# Module_BaseBoard.net
KiCad netlist of a schematic drawn in EAGLE
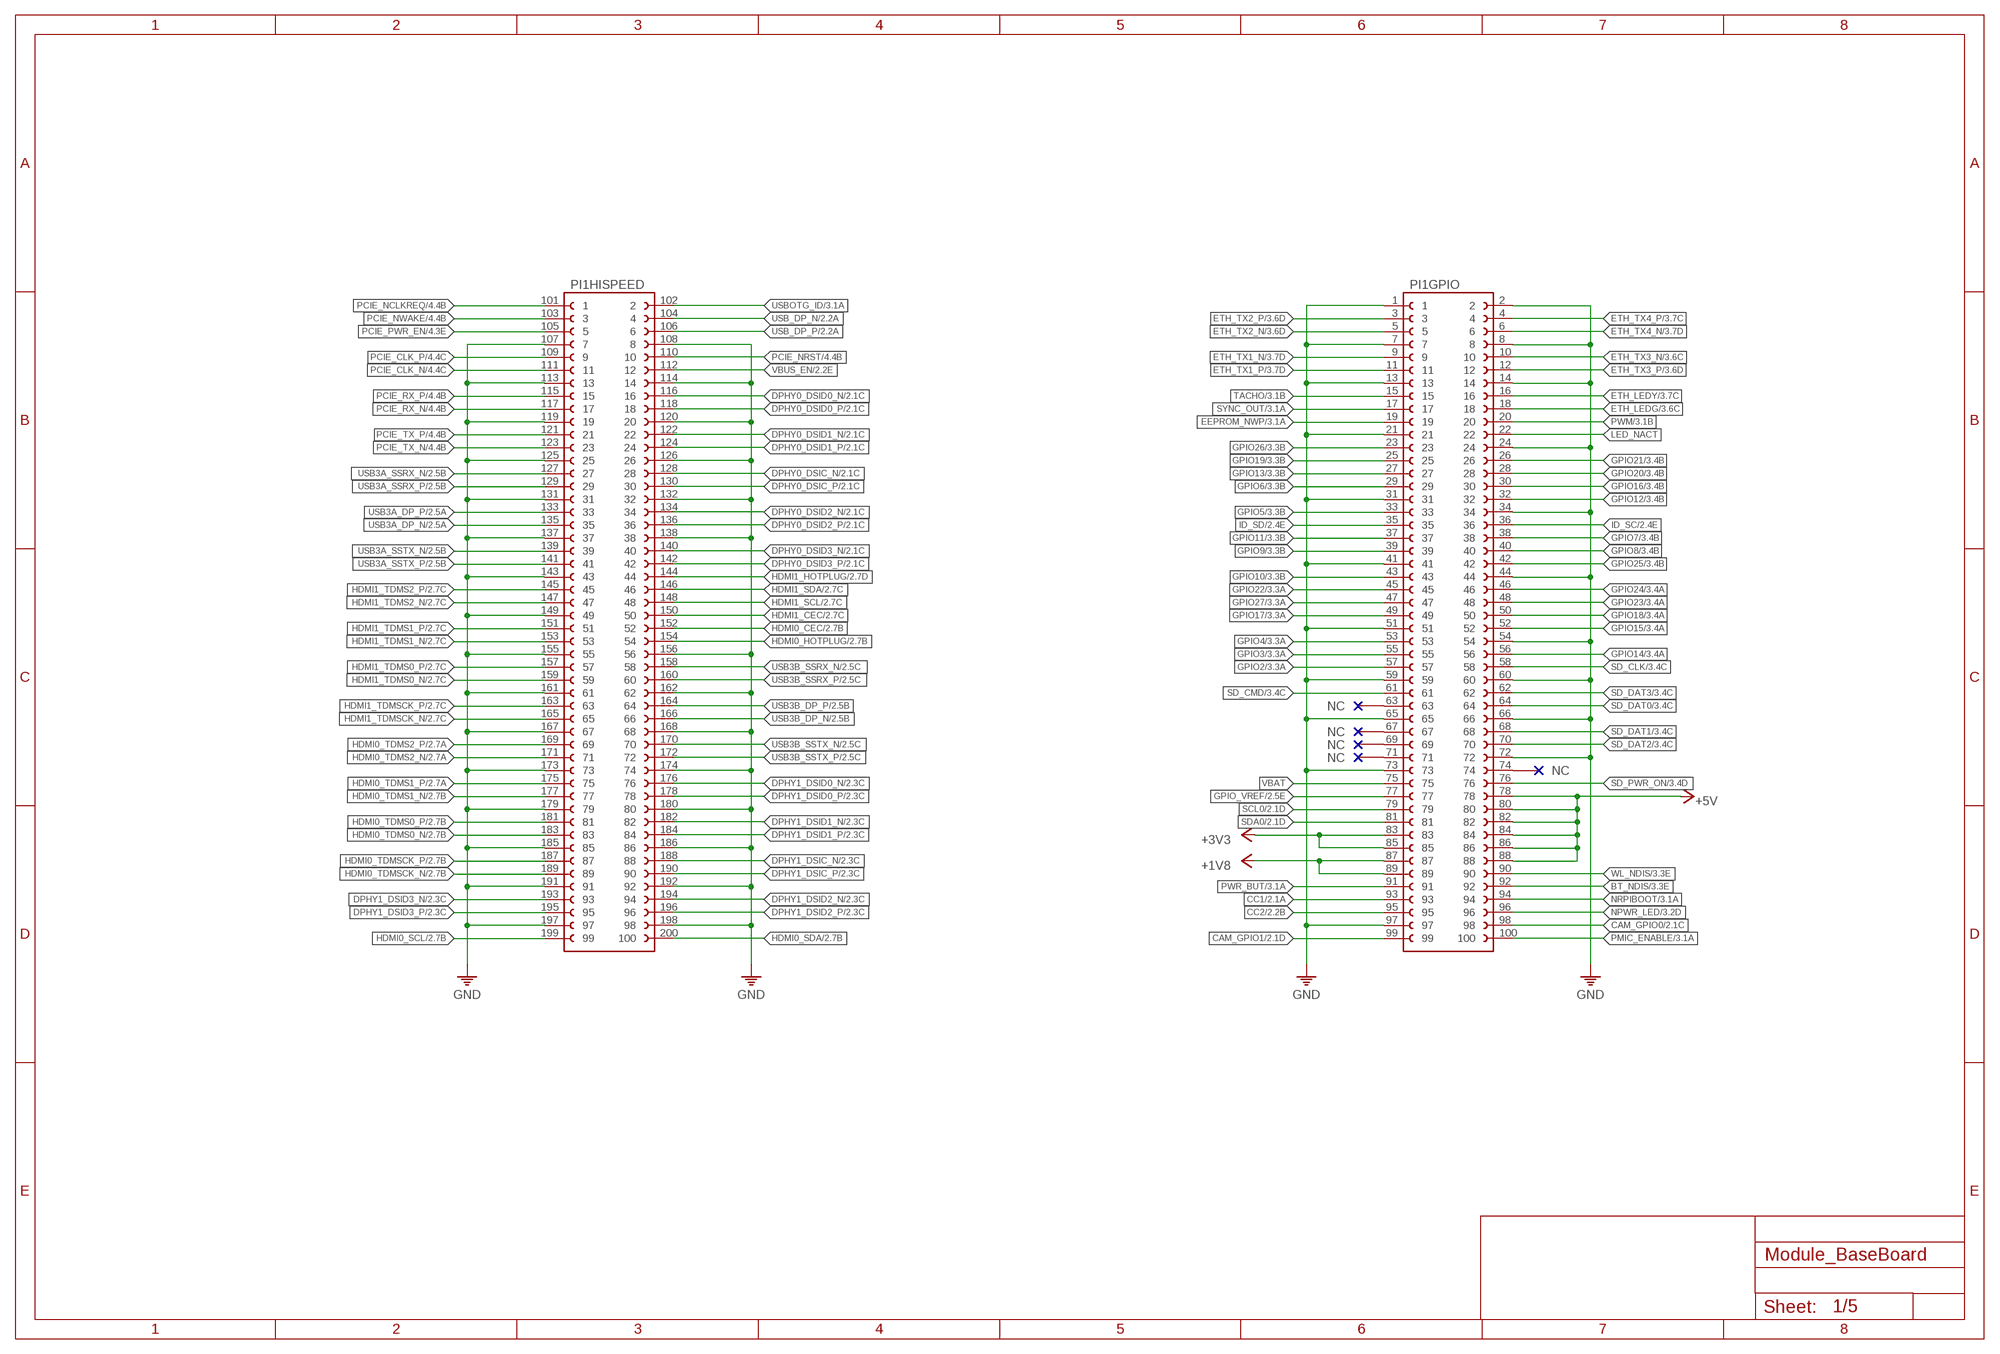
[diagram p0: schematic, sheet 1]
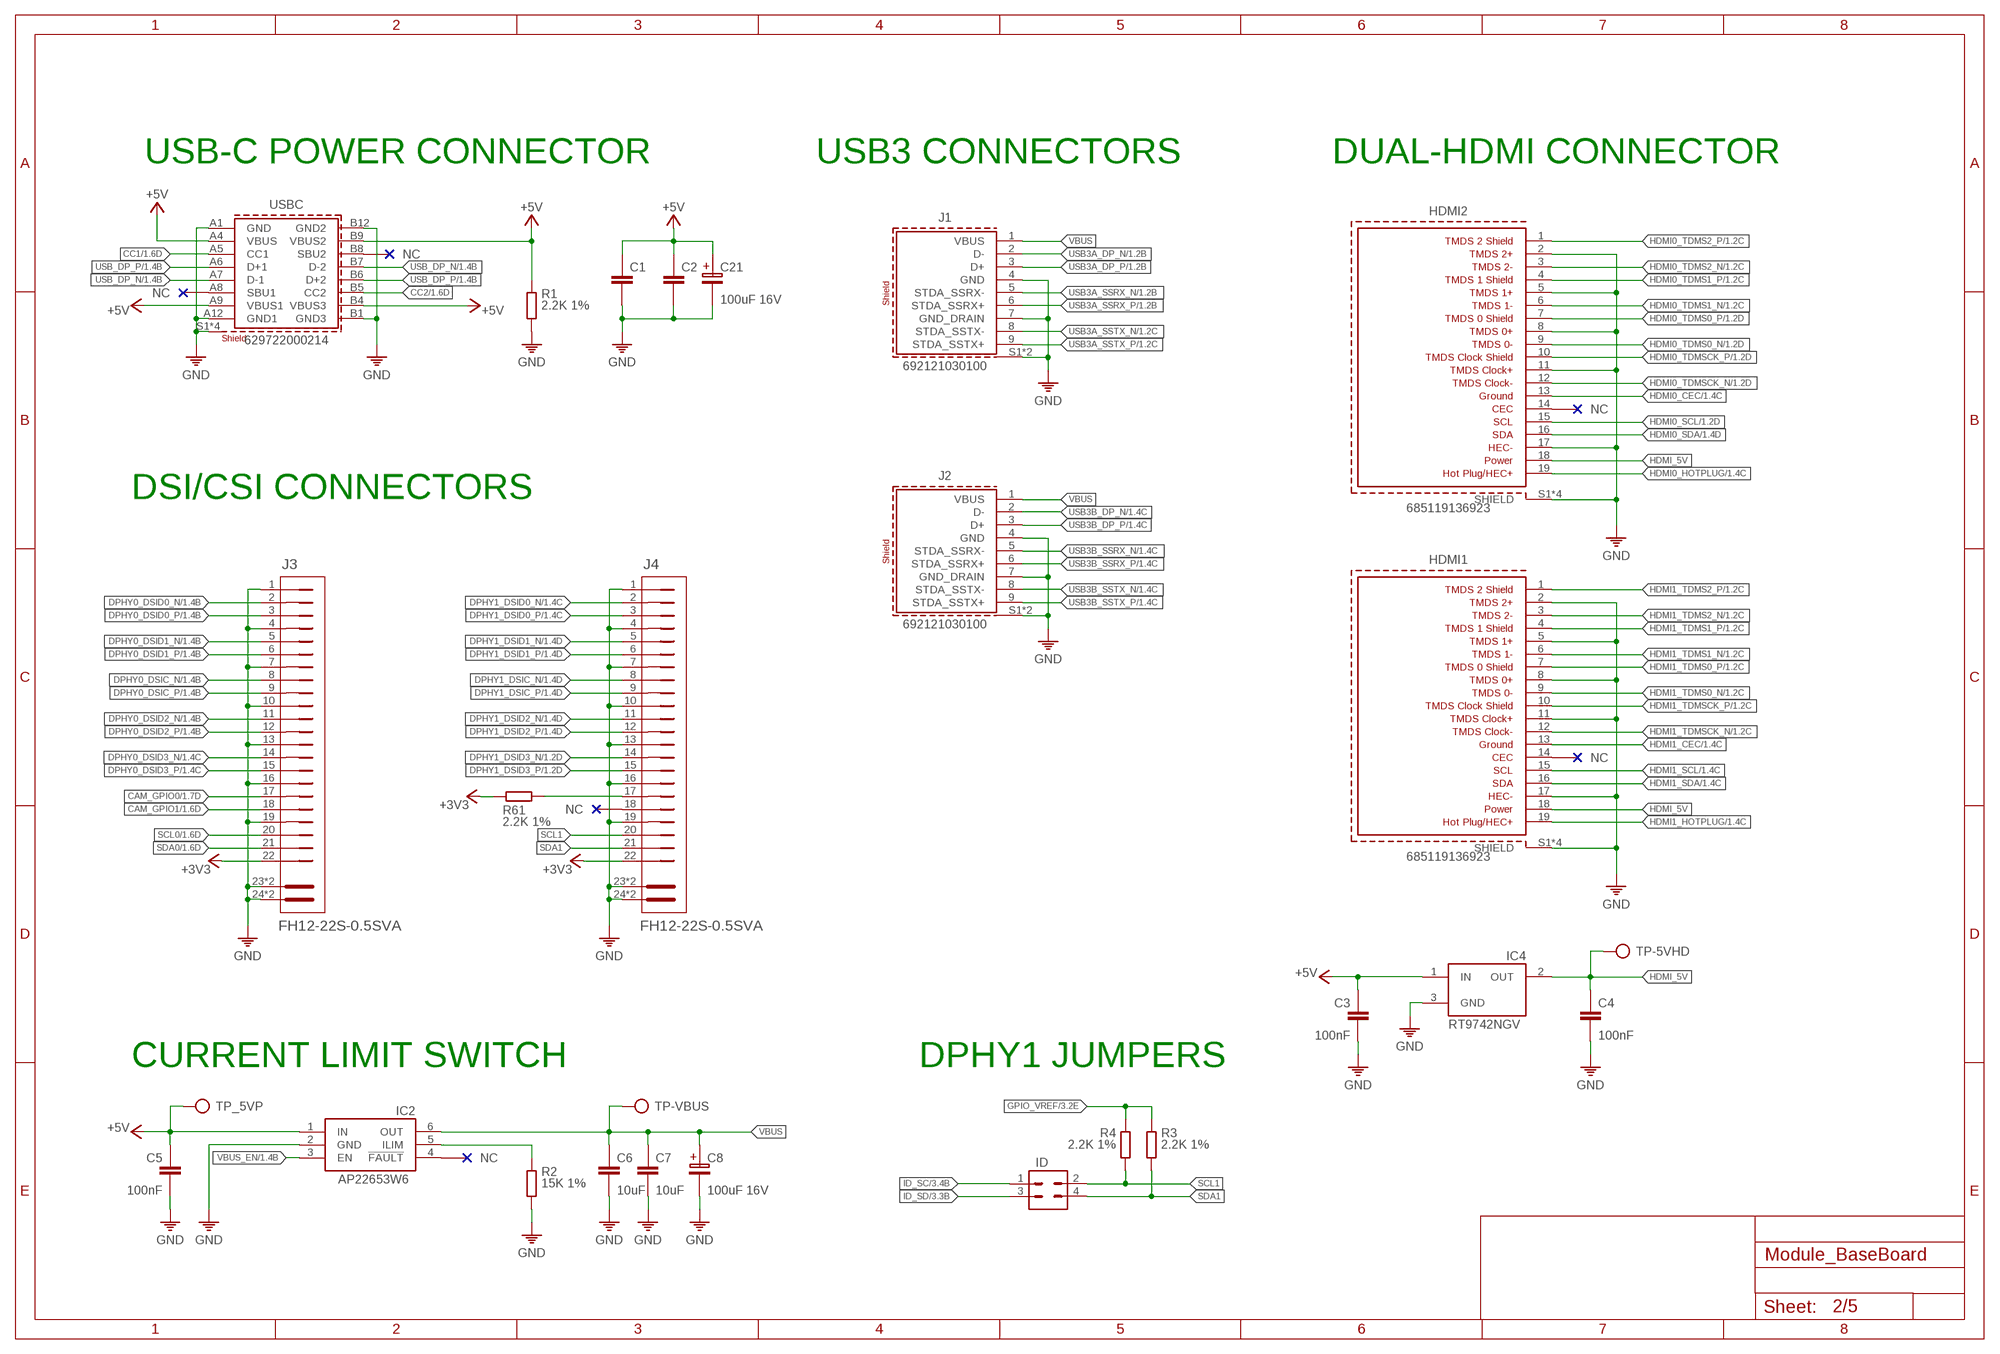
[diagram p1: schematic, sheet 2]
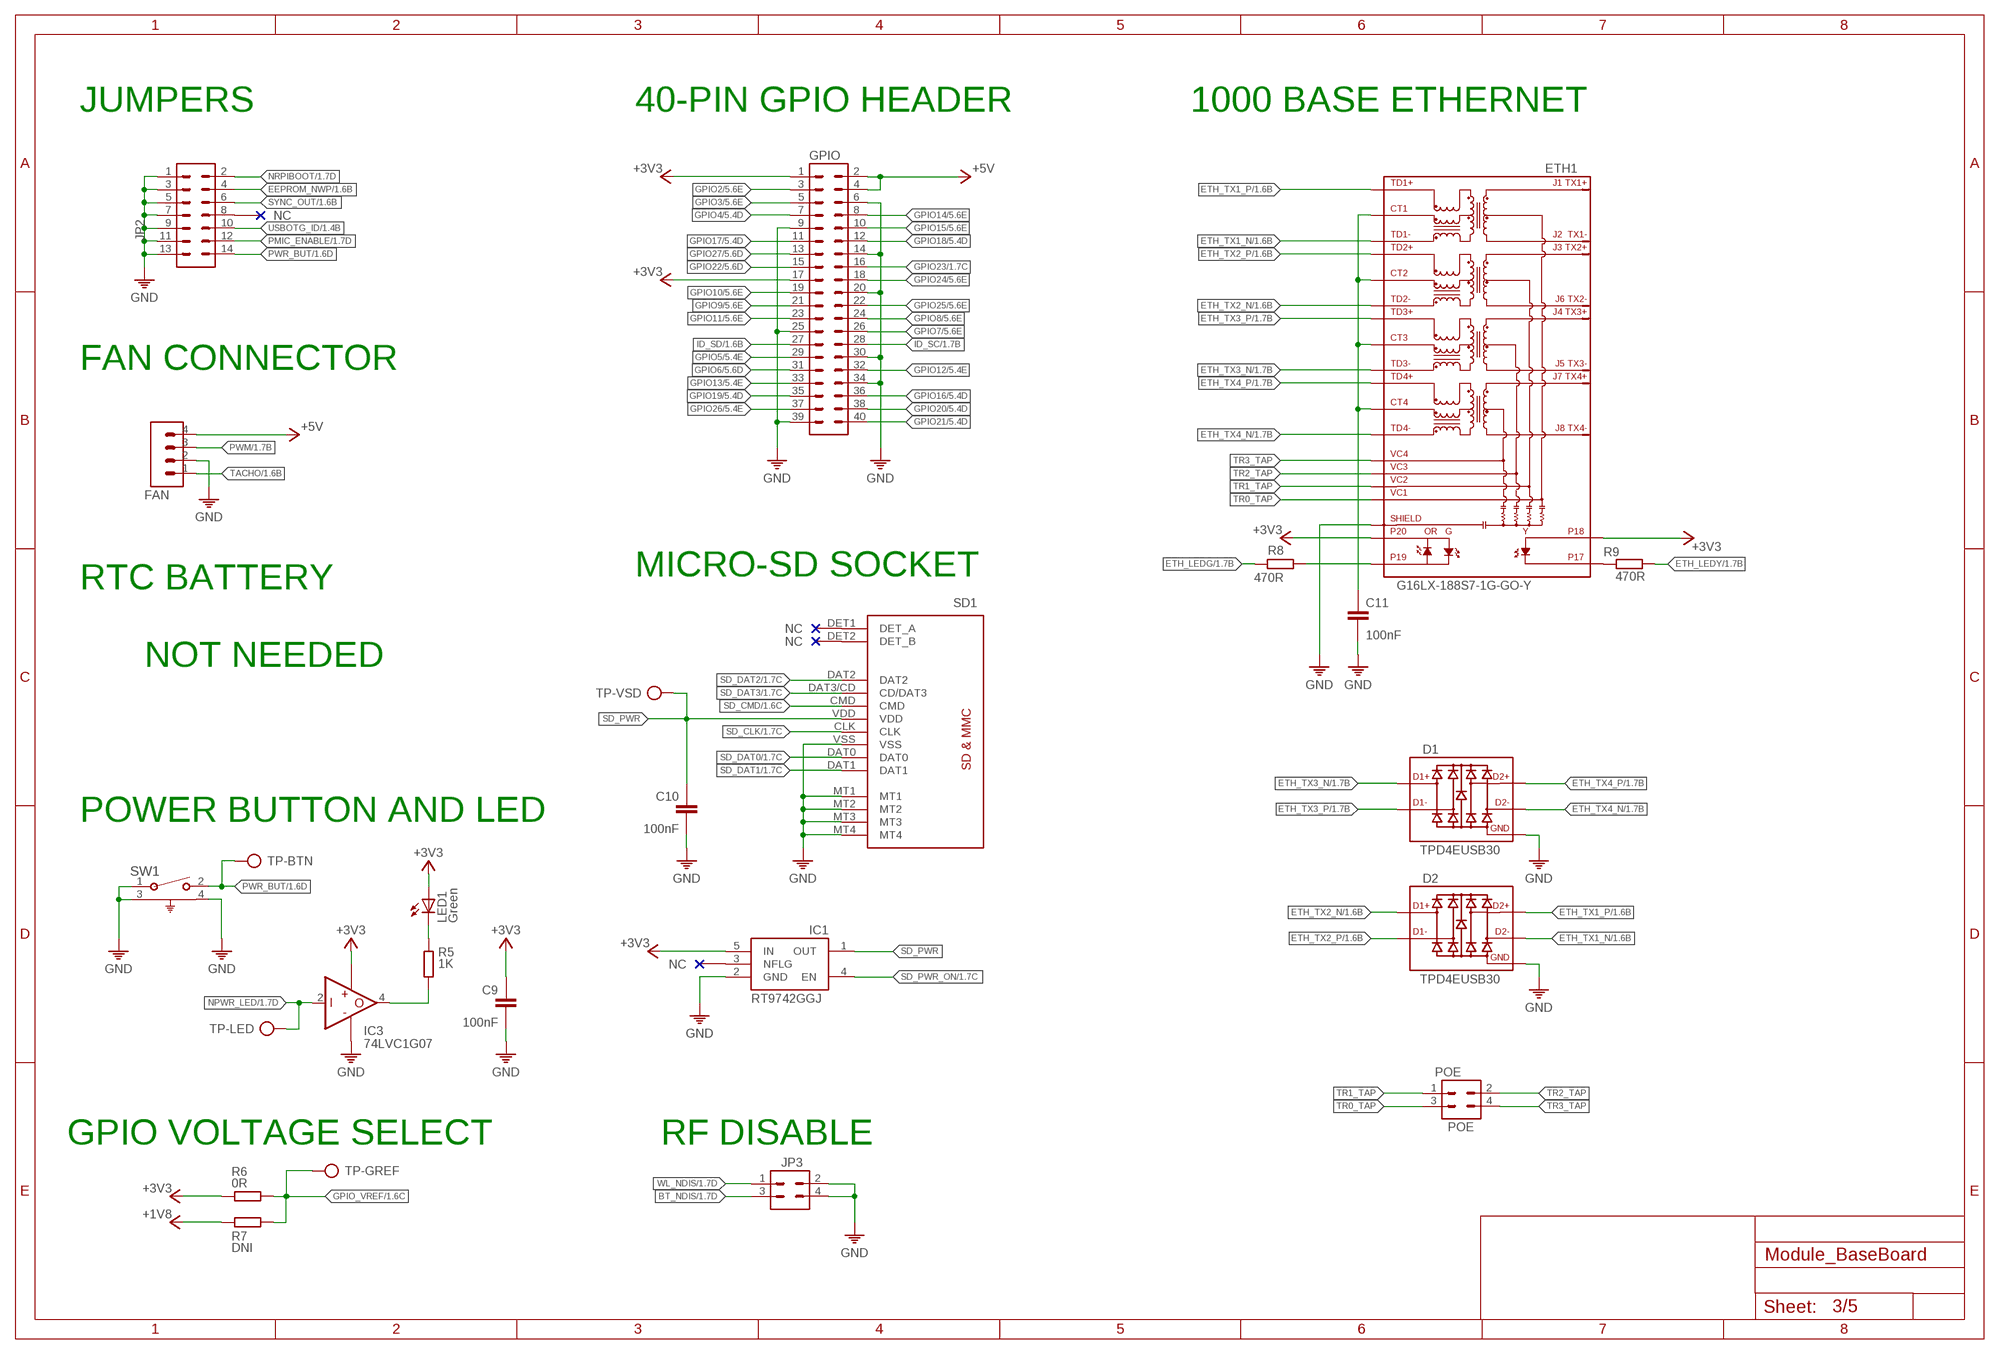
[diagram p2: schematic, sheet 3]
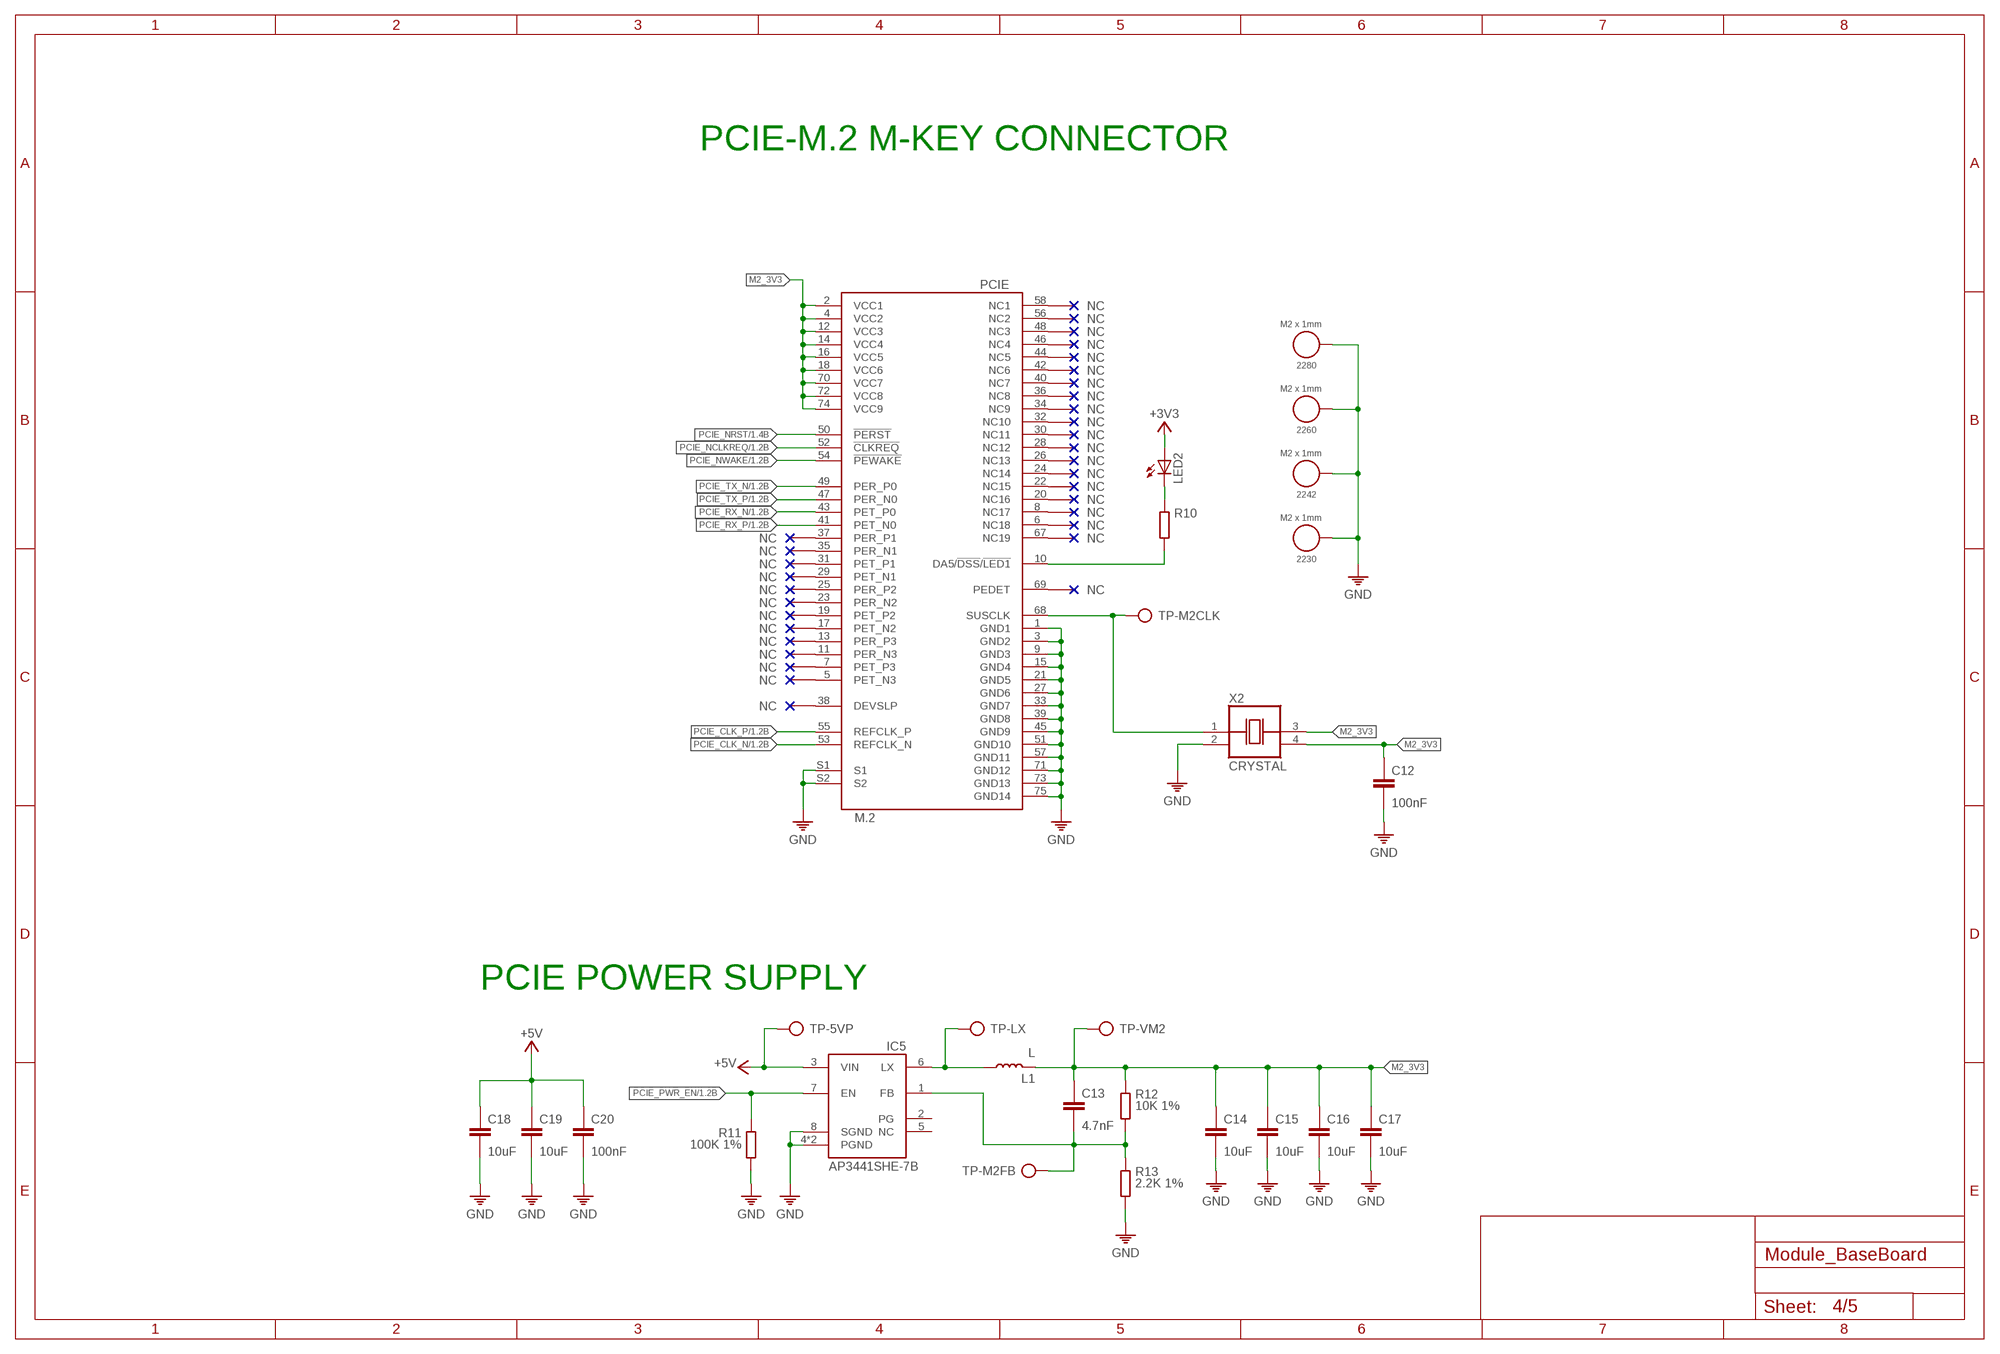
[diagram p3: schematic, sheet 4]
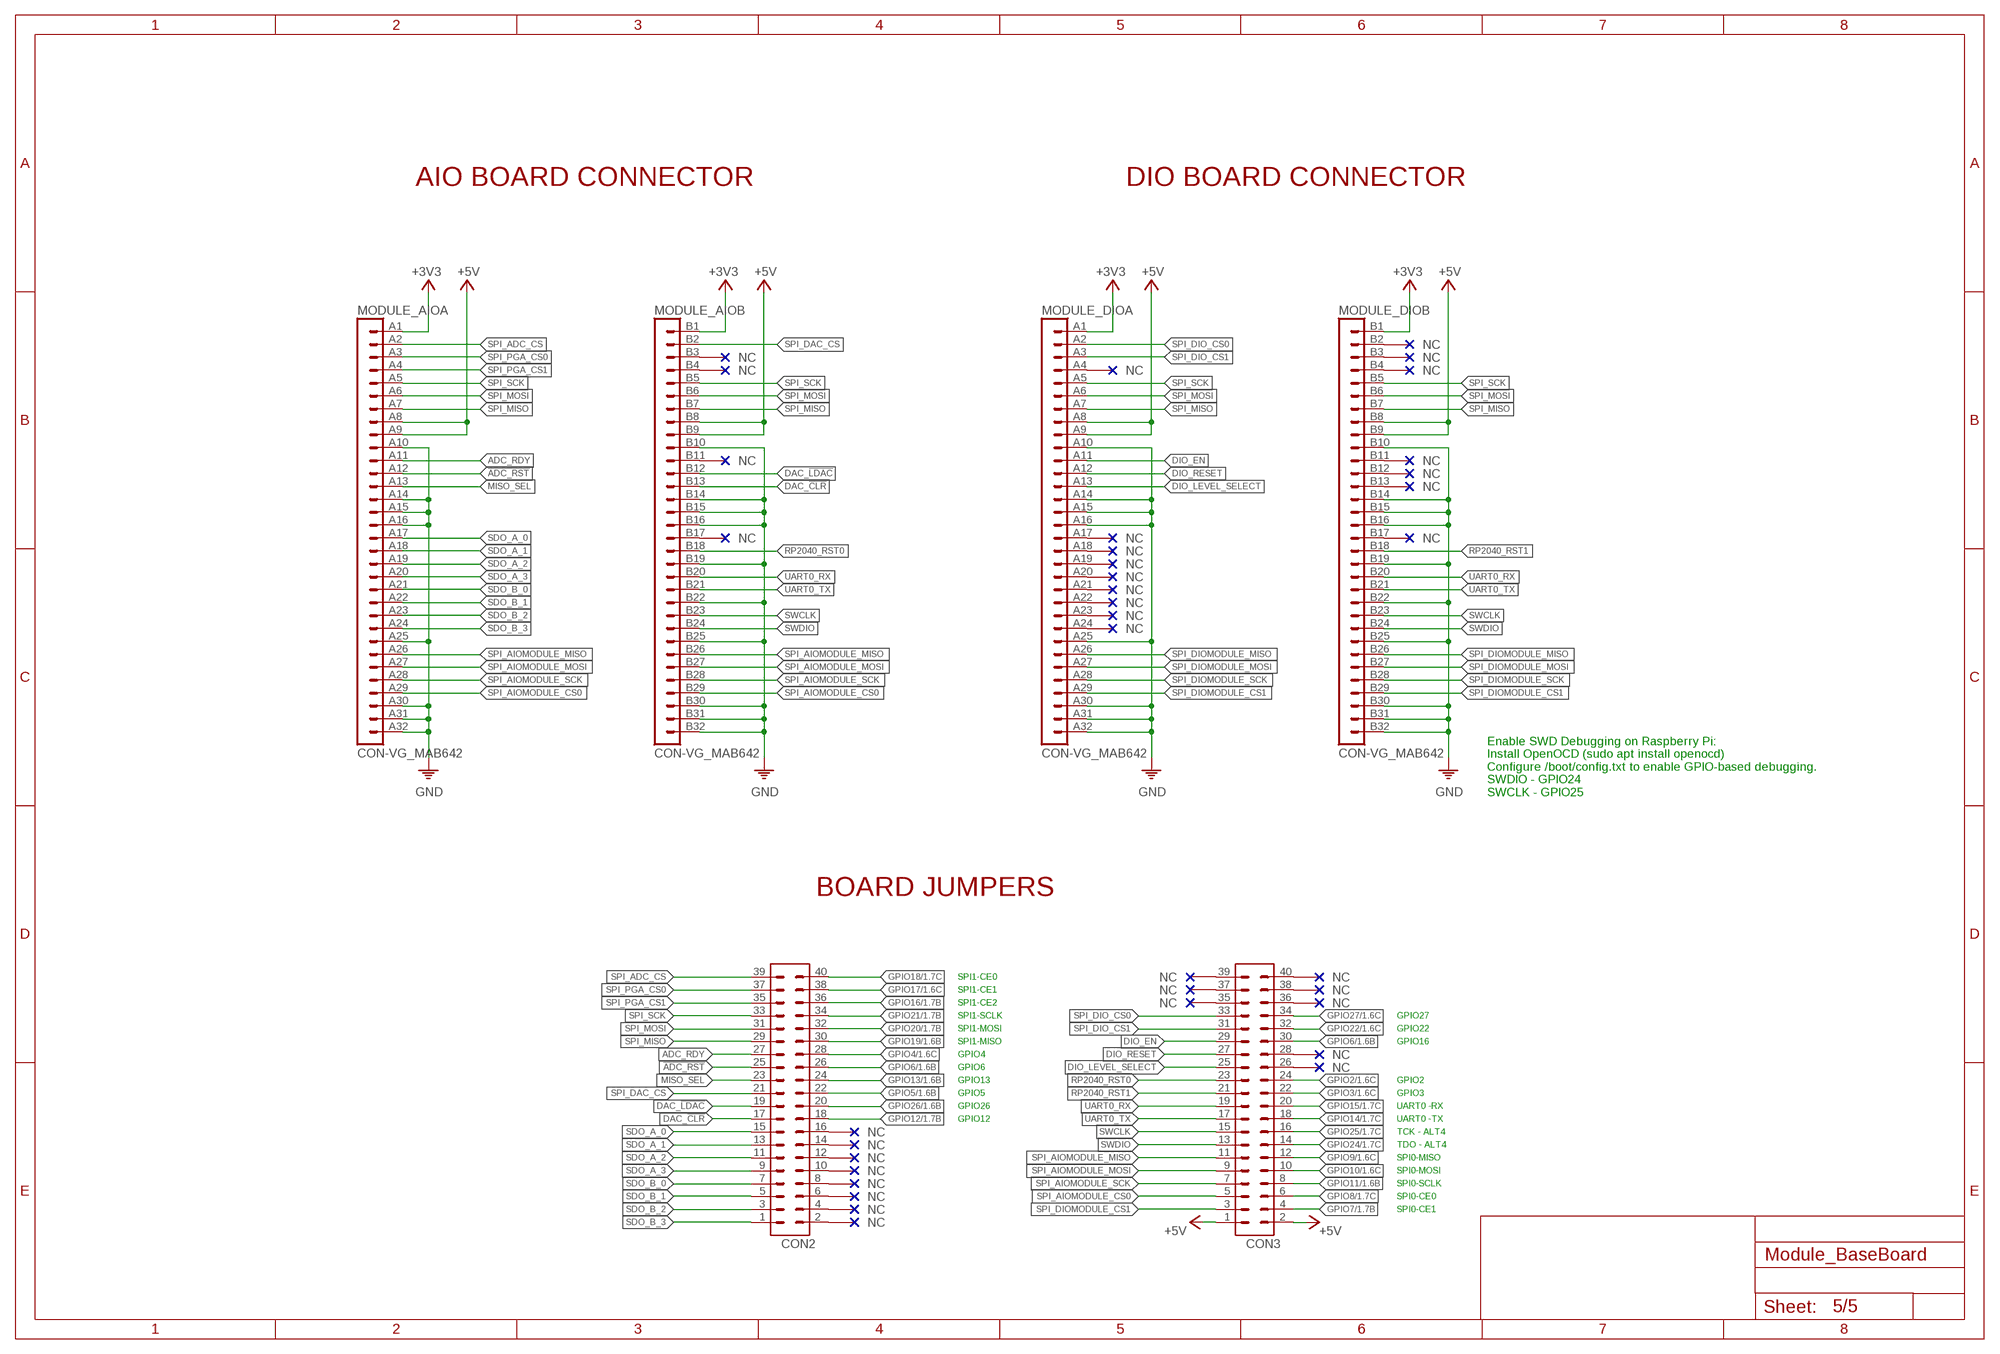
[diagram p4: schematic, sheet 5]

(export (version "E")
  (design (tool "Eeschema 10.0.6"))
  (components
    (comp (ref "2230")
      (value "M2 x 1mm")
      (footprint "eagle-import:WA-SMSI_9774010243")
      (libsource (lib "eagle-import") (part "WA-SMSI_9774XXX243_9774010243"))
    )
    (comp (ref "2242")
      (value "M2 x 1mm")
      (footprint "eagle-import:WA-SMSI_9774010243")
      (libsource (lib "eagle-import") (part "WA-SMSI_9774XXX243_9774010243"))
    )
    (comp (ref "2260")
      (value "M2 x 1mm")
      (footprint "eagle-import:WA-SMSI_9774010243")
      (libsource (lib "eagle-import") (part "WA-SMSI_9774XXX243_9774010243"))
    )
    (comp (ref "2280")
      (value "M2 x 1mm")
      (footprint "eagle-import:WA-SMSI_9774010243")
      (libsource (lib "eagle-import") (part "WA-SMSI_9774XXX243_9774010243"))
    )
    (comp (ref "C12")
      (value "100nF")
      (footprint "eagle-import:C0402")
      (libsource (lib "eagle-import") (part "C-0402"))
    )
    (comp (ref "C13")
      (value "4.7nF")
      (footprint "eagle-import:C0402")
      (libsource (lib "eagle-import") (part "C-0402"))
    )
    (comp (ref "C14")
      (value "10uF")
      (footprint "eagle-import:C0805")
      (libsource (lib "eagle-import") (part "C-0805"))
    )
    (comp (ref "C15")
      (value "10uF")
      (footprint "eagle-import:C0805")
      (libsource (lib "eagle-import") (part "C-0805"))
    )
    (comp (ref "C16")
      (value "10uF")
      (footprint "eagle-import:C0805")
      (libsource (lib "eagle-import") (part "C-0805"))
    )
    (comp (ref "C17")
      (value "10uF")
      (footprint "eagle-import:C0805")
      (libsource (lib "eagle-import") (part "C-0805"))
    )
    (comp (ref "C18")
      (value "10uF")
      (footprint "eagle-import:C0805")
      (libsource (lib "eagle-import") (part "C-0805"))
    )
    (comp (ref "C19")
      (value "10uF")
      (footprint "eagle-import:C0805")
      (libsource (lib "eagle-import") (part "C-0805"))
    )
    (comp (ref "C20")
      (value "100nF")
      (footprint "eagle-import:C0402")
      (libsource (lib "eagle-import") (part "C-0402"))
    )
    (comp (ref "IC5")
      (value "AP3441SHE-7B")
      (footprint "eagle-import:SON50P201X201X56-9T90X170N")
      (libsource (lib "eagle-import") (part "AP3441SHE-7B"))
    )
    (comp (ref "L1")
      (value "L")
      (footprint "eagle-import:SRR5228A")
      (libsource (lib "eagle-import") (part "L"))
    )
    (comp (ref "LED2")
      (value "LEDCHIPLED_0805")
      (footprint "eagle-import:CHIPLED_0805")
      (libsource (lib "eagle-import") (part "LEDCHIPLED_0805"))
    )
    (comp (ref "PCIE")
      (value "M.2")
      (footprint "eagle-import:M.2")
      (libsource (lib "eagle-import") (part "M.2"))
    )
    (comp (ref "R10")
      (value "R0402")
      (footprint "eagle-import:0402")
      (libsource (lib "eagle-import") (part "R0402"))
    )
    (comp (ref "R11")
      (value "100K 1%")
      (footprint "eagle-import:0402")
      (libsource (lib "eagle-import") (part "R0402"))
    )
    (comp (ref "R12")
      (value "10K 1%")
      (footprint "eagle-import:0402")
      (libsource (lib "eagle-import") (part "R0402"))
    )
    (comp (ref "R13")
      (value "2.2K 1%")
      (footprint "eagle-import:0402")
      (libsource (lib "eagle-import") (part "R0402"))
    )
    (comp (ref "TP-5VP")
      (value "TP")
      (footprint "eagle-import:TP")
      (libsource (lib "eagle-import") (part "TP"))
    )
    (comp (ref "TP-LX")
      (value "TP")
      (footprint "eagle-import:TP")
      (libsource (lib "eagle-import") (part "TP"))
    )
    (comp (ref "TP-M2CLK")
      (value "TP")
      (footprint "eagle-import:TP")
      (libsource (lib "eagle-import") (part "TP"))
    )
    (comp (ref "TP-M2FB")
      (value "TP")
      (footprint "eagle-import:TP")
      (libsource (lib "eagle-import") (part "TP"))
    )
    (comp (ref "TP-VM2")
      (value "TP")
      (footprint "eagle-import:TP")
      (libsource (lib "eagle-import") (part "TP"))
    )
    (comp (ref "X2")
      (value "CRYSTAL")
      (footprint "eagle-import:OSCCC500X320X130")
      (libsource (lib "eagle-import") (part "CRYSTAL"))
    )
    (comp (ref "C9")
      (value "100nF")
      (footprint "eagle-import:C0402")
      (libsource (lib "eagle-import") (part "C-0402"))
    )
    (comp (ref "C10")
      (value "100nF")
      (footprint "eagle-import:C0402")
      (libsource (lib "eagle-import") (part "C-0402"))
    )
    (comp (ref "C11")
      (value "100nF")
      (footprint "eagle-import:C0402")
      (libsource (lib "eagle-import") (part "C-0402"))
    )
    (comp (ref "D1")
      (value "TPD4EUSB30")
      (footprint "eagle-import:USON")
      (libsource (lib "eagle-import") (part "TPD4EUSB30"))
    )
    (comp (ref "D2")
      (value "TPD4EUSB30")
      (footprint "eagle-import:USON")
      (libsource (lib "eagle-import") (part "TPD4EUSB30"))
    )
    (comp (ref "ETH1")
      (value "G16LX-188S7-1G-GO-Y")
      (footprint "eagle-import:MAGJACK_POE")
      (libsource (lib "eagle-import") (part "MAGJACK-POE"))
    )
    (comp (ref "FAN")
      (value "CON-1X4")
      (footprint "eagle-import:1X4")
      (libsource (lib "eagle-import") (part "CON-1X4"))
    )
    (comp (ref "GPIO")
      (value "CON-2X20")
      (footprint "eagle-import:2X20")
      (libsource (lib "eagle-import") (part "CON-2X20"))
    )
    (comp (ref "IC1")
      (value "RT9742GGJ")
      (footprint "eagle-import:SOT23-5")
      (libsource (lib "eagle-import") (part "RT9742GGJ5"))
    )
    (comp (ref "IC3")
      (value "74LVC1G07")
      (footprint "eagle-import:SOT23-5")
      (libsource (lib "eagle-import") (part "74LVC1G07"))
    )
    (comp (ref "JP2")
      (value "CON-2X7")
      (footprint "eagle-import:2X7")
      (libsource (lib "eagle-import") (part "CON-2X7"))
    )
    (comp (ref "JP3")
      (value "CON-2X2")
      (footprint "eagle-import:2X2")
      (libsource (lib "eagle-import") (part "CON-2X2"))
    )
    (comp (ref "LED1")
      (value "Green")
      (footprint "eagle-import:CHIPLED_0805")
      (libsource (lib "eagle-import") (part "LEDCHIPLED_0805"))
    )
    (comp (ref "POE")
      (value "POE")
      (footprint "eagle-import:2X2")
      (libsource (lib "eagle-import") (part "CON-2X2"))
    )
    (comp (ref "R5")
      (value "1K")
      (footprint "eagle-import:0402")
      (libsource (lib "eagle-import") (part "R0402"))
    )
    (comp (ref "R6")
      (value "0R")
      (footprint "eagle-import:0402")
      (libsource (lib "eagle-import") (part "R0402"))
    )
    (comp (ref "R7")
      (value "DNI")
      (footprint "eagle-import:0402")
      (libsource (lib "eagle-import") (part "R0402"))
    )
    (comp (ref "R8")
      (value "470R")
      (footprint "eagle-import:0402")
      (libsource (lib "eagle-import") (part "R0402"))
    )
    (comp (ref "R9")
      (value "470R")
      (footprint "eagle-import:0402")
      (libsource (lib "eagle-import") (part "R0402"))
    )
    (comp (ref "SD1")
      (value "MICRO-SD")
      (footprint "eagle-import:MICROSD")
      (libsource (lib "eagle-import") (part "MICRO-SD"))
    )
    (comp (ref "SW1")
      (value "1825027-8")
      (footprint "eagle-import:SW2_1825027-C_TEC")
      (fields (field (name "COPYRIGHT") "Copyright (C) 2025 Ultra Librarian. All rights reserved."))
      (libsource (lib "eagle-import") (part "1825027-8"))
    )
    (comp (ref "TP-BTN")
      (value "TP")
      (footprint "eagle-import:TP")
      (libsource (lib "eagle-import") (part "TP"))
    )
    (comp (ref "TP-GREF")
      (value "TP")
      (footprint "eagle-import:TP")
      (libsource (lib "eagle-import") (part "TP"))
    )
    (comp (ref "TP-LED")
      (value "TP")
      (footprint "eagle-import:TP")
      (libsource (lib "eagle-import") (part "TP"))
    )
    (comp (ref "TP-VSD")
      (value "TP")
      (footprint "eagle-import:TP")
      (libsource (lib "eagle-import") (part "TP"))
    )
    (comp (ref "PI1")
      (value "RASPBERRY_CM5")
      (footprint "eagle-import:CM5")
      (libsource (lib "eagle-import") (part "RASPBERRY_CM5"))
    )
    (comp (ref "CON2")
      (value "CON-2X20")
      (footprint "eagle-import:2X20")
      (libsource (lib "eagle-import") (part "CON-2X20"))
    )
    (comp (ref "CON3")
      (value "CON-2X20")
      (footprint "eagle-import:2X20")
      (libsource (lib "eagle-import") (part "CON-2X20"))
    )
    (comp (ref "MODULE_AIO")
      (value "CON-VG_MAB642")
      (footprint "eagle-import:CON-VG-MAB64-RECEPTACLE")
      (libsource (lib "eagle-import") (part "CON-VG_MAB642"))
    )
    (comp (ref "MODULE_DIO")
      (value "CON-VG_MAB642")
      (footprint "eagle-import:CON-VG-MAB64-RECEPTACLE")
      (libsource (lib "eagle-import") (part "CON-VG_MAB642"))
    )
    (comp (ref "C1")
      (value "C-0402")
      (footprint "eagle-import:C0402")
      (libsource (lib "eagle-import") (part "C-0402"))
    )
    (comp (ref "C2")
      (value "C-0402")
      (footprint "eagle-import:C0402")
      (libsource (lib "eagle-import") (part "C-0402"))
    )
    (comp (ref "C3")
      (value "100nF")
      (footprint "eagle-import:C0402")
      (libsource (lib "eagle-import") (part "C-0402"))
    )
    (comp (ref "C4")
      (value "100nF")
      (footprint "eagle-import:C0402")
      (libsource (lib "eagle-import") (part "C-0402"))
    )
    (comp (ref "C5")
      (value "100nF")
      (footprint "eagle-import:C0402")
      (libsource (lib "eagle-import") (part "C-0402"))
    )
    (comp (ref "C6")
      (value "10uF")
      (footprint "eagle-import:C0805")
      (libsource (lib "eagle-import") (part "C-0805"))
    )
    (comp (ref "C7")
      (value "10uF")
      (footprint "eagle-import:C0805")
      (libsource (lib "eagle-import") (part "C-0805"))
    )
    (comp (ref "C8")
      (value "100uF 16V")
      (footprint "eagle-import:100UF-16V")
      (libsource (lib "eagle-import") (part "CPOL"))
    )
    (comp (ref "C21")
      (value "100uF 16V")
      (footprint "eagle-import:100UF-16V")
      (libsource (lib "eagle-import") (part "CPOL"))
    )
    (comp (ref "HDMI1")
      (value "685119136923")
      (footprint "eagle-import:685119136923")
      (libsource (lib "eagle-import") (part "685119136923"))
    )
    (comp (ref "HDMI2")
      (value "685119136923")
      (footprint "eagle-import:685119136923")
      (libsource (lib "eagle-import") (part "685119136923"))
    )
    (comp (ref "IC2")
      (value "AP22653W6")
      (footprint "eagle-import:SOT23-6")
      (libsource (lib "eagle-import") (part "AP22653W6"))
    )
    (comp (ref "IC4")
      (value "RT9742NGV")
      (footprint "eagle-import:SOT23")
      (libsource (lib "eagle-import") (part "RT9742NGV"))
    )
    (comp (ref "ID")
      (value "CON-2X2")
      (footprint "eagle-import:2X2")
      (libsource (lib "eagle-import") (part "CON-2X2"))
    )
    (comp (ref "J1")
      (value "692121030100")
      (footprint "eagle-import:692121030100")
      (libsource (lib "eagle-import") (part "692121030100"))
    )
    (comp (ref "J2")
      (value "692121030100")
      (footprint "eagle-import:692121030100")
      (libsource (lib "eagle-import") (part "692121030100"))
    )
    (comp (ref "J3")
      (value "FH12-22S-0.5SVA")
      (footprint "eagle-import:FH12-22S-0.5SH")
      (libsource (lib "eagle-import") (part "FH12-22S-0.5SVA"))
    )
    (comp (ref "J4")
      (value "FH12-22S-0.5SVA")
      (footprint "eagle-import:FH12-22S-0.5SH")
      (libsource (lib "eagle-import") (part "FH12-22S-0.5SVA"))
    )
    (comp (ref "R1")
      (value "2.2K 1%")
      (footprint "eagle-import:0402")
      (libsource (lib "eagle-import") (part "R0402"))
    )
    (comp (ref "R2")
      (value "15K 1%")
      (footprint "eagle-import:0402")
      (libsource (lib "eagle-import") (part "R0402"))
    )
    (comp (ref "R3")
      (value "2.2K 1%")
      (footprint "eagle-import:0402")
      (libsource (lib "eagle-import") (part "R0402"))
    )
    (comp (ref "R4")
      (value "2.2K 1%")
      (footprint "eagle-import:0402")
      (libsource (lib "eagle-import") (part "R0402"))
    )
    (comp (ref "R61")
      (value "2.2K 1%")
      (footprint "eagle-import:0402")
      (libsource (lib "eagle-import") (part "ds_passive_46685041_R0402"))
    )
    (comp (ref "TP-5VHD")
      (value "TP")
      (footprint "eagle-import:TP")
      (libsource (lib "eagle-import") (part "TP"))
    )
    (comp (ref "TP-VBUS")
      (value "TP")
      (footprint "eagle-import:TP")
      (libsource (lib "eagle-import") (part "TP"))
    )
    (comp (ref "TP_5VP")
      (value "TP")
      (footprint "eagle-import:TP")
      (libsource (lib "eagle-import") (part "TP"))
    )
    (comp (ref "USBC")
      (value "629722000214")
      (footprint "eagle-import:629722000214")
      (libsource (lib "eagle-import") (part "629722000214"))
    )
  )
  (nets
    (net (code "1") (name "+1V8") (class "Default")
      (node (ref "PI1") (pin "87") (pinfunction "87_87") (pintype "passive"))
      (node (ref "PI1") (pin "89") (pinfunction "89_89") (pintype "passive"))
      (node (ref "R7") (pin "1") (pinfunction "1_1") (pintype "passive"))
    )
    (net (code "2") (name "+3V3") (class "Default")
      (node (ref "C9") (pin "1") (pinfunction "1_1") (pintype "passive"))
      (node (ref "ETH1") (pin "18") (pinfunction "P18_18") (pintype "bidirectional"))
      (node (ref "ETH1") (pin "20") (pinfunction "P20_20") (pintype "bidirectional"))
      (node (ref "GPIO") (pin "1") (pinfunction "1_1") (pintype "bidirectional"))
      (node (ref "GPIO") (pin "17") (pinfunction "17_17") (pintype "bidirectional"))
      (node (ref "IC1") (pin "5") (pinfunction "IN_5") (pintype "power_in"))
      (node (ref "IC3") (pin "5") (pinfunction "VCC_5") (pintype "bidirectional"))
      (node (ref "J3") (pin "22") (pinfunction "22_22") (pintype "passive"))
      (node (ref "J4") (pin "22") (pinfunction "22_22") (pintype "passive"))
      (node (ref "LED1") (pin "A") (pinfunction "A_A") (pintype "passive"))
      (node (ref "LED2") (pin "A") (pinfunction "A_A") (pintype "passive"))
      (node (ref "MODULE_AIO") (pin "A1") (pinfunction "1_A1") (pintype "passive"))
      (node (ref "MODULE_AIO") (pin "B1") (pinfunction "1_B1") (pintype "passive"))
      (node (ref "MODULE_DIO") (pin "A1") (pinfunction "1_A1") (pintype "passive"))
      (node (ref "MODULE_DIO") (pin "B1") (pinfunction "1_B1") (pintype "passive"))
      (node (ref "PI1") (pin "83") (pinfunction "83_83") (pintype "passive"))
      (node (ref "PI1") (pin "85") (pinfunction "85_85") (pintype "passive"))
      (node (ref "R6") (pin "1") (pinfunction "1_1") (pintype "passive"))
      (node (ref "R61") (pin "2") (pinfunction "2_2") (pintype "passive"))
    )
    (net (code "3") (name "+5V") (class "Default")
      (node (ref "C1") (pin "1") (pinfunction "1_1") (pintype "passive"))
      (node (ref "C18") (pin "1") (pinfunction "1_1") (pintype "passive"))
      (node (ref "C19") (pin "1") (pinfunction "1_1") (pintype "passive"))
      (node (ref "C2") (pin "1") (pinfunction "1_1") (pintype "passive"))
      (node (ref "C20") (pin "1") (pinfunction "1_1") (pintype "passive"))
      (node (ref "C21") (pin "1") (pinfunction "1_1") (pintype "passive"))
      (node (ref "C3") (pin "1") (pinfunction "1_1") (pintype "passive"))
      (node (ref "C5") (pin "1") (pinfunction "1_1") (pintype "passive"))
      (node (ref "CON3") (pin "1") (pinfunction "1_1") (pintype "bidirectional"))
      (node (ref "CON3") (pin "2") (pinfunction "2_2") (pintype "bidirectional"))
      (node (ref "FAN") (pin "4") (pinfunction "P$4_4") (pintype "bidirectional"))
      (node (ref "GPIO") (pin "2") (pinfunction "2_2") (pintype "bidirectional"))
      (node (ref "GPIO") (pin "4") (pinfunction "4_4") (pintype "bidirectional"))
      (node (ref "IC2") (pin "1") (pinfunction "IN_1") (pintype "bidirectional"))
      (node (ref "IC4") (pin "1") (pinfunction "IN_1") (pintype "power_in"))
      (node (ref "IC5") (pin "3") (pinfunction "VIN_3") (pintype "power_in"))
      (node (ref "MODULE_AIO") (pin "A8") (pinfunction "8_A8") (pintype "passive"))
      (node (ref "MODULE_AIO") (pin "A9") (pinfunction "9_A9") (pintype "passive"))
      (node (ref "MODULE_AIO") (pin "B8") (pinfunction "8_B8") (pintype "passive"))
      (node (ref "MODULE_AIO") (pin "B9") (pinfunction "9_B9") (pintype "passive"))
      (node (ref "MODULE_DIO") (pin "A8") (pinfunction "8_A8") (pintype "passive"))
      (node (ref "MODULE_DIO") (pin "A9") (pinfunction "9_A9") (pintype "passive"))
      (node (ref "MODULE_DIO") (pin "B8") (pinfunction "8_B8") (pintype "passive"))
      (node (ref "MODULE_DIO") (pin "B9") (pinfunction "9_B9") (pintype "passive"))
      (node (ref "PI1") (pin "78") (pinfunction "78_78") (pintype "passive"))
      (node (ref "PI1") (pin "80") (pinfunction "80_80") (pintype "passive"))
      (node (ref "PI1") (pin "82") (pinfunction "82_82") (pintype "passive"))
      (node (ref "PI1") (pin "84") (pinfunction "84_84") (pintype "passive"))
      (node (ref "PI1") (pin "86") (pinfunction "86_86") (pintype "passive"))
      (node (ref "PI1") (pin "88") (pinfunction "88_88") (pintype "passive"))
      (node (ref "R1") (pin "1") (pinfunction "1_1") (pintype "passive"))
      (node (ref "TP-5VP") (pin "TP") (pinfunction "P$1_TP") (pintype "bidirectional"))
      (node (ref "TP_5VP") (pin "TP") (pinfunction "P$1_TP") (pintype "bidirectional"))
      (node (ref "USBC") (pin "A4") (pinfunction "VBUS_A4") (pintype "passive"))
      (node (ref "USBC") (pin "A9") (pinfunction "VBUS1_A9") (pintype "passive"))
      (node (ref "USBC") (pin "B4") (pinfunction "VBUS3_B4") (pintype "passive"))
      (node (ref "USBC") (pin "B9") (pinfunction "VBUS2_B9") (pintype "passive"))
    )
    (net (code "4") (name "ADC_RDY") (class "Default")
      (node (ref "CON2") (pin "27") (pinfunction "27_27") (pintype "bidirectional"))
      (node (ref "MODULE_AIO") (pin "A11") (pinfunction "11_A11") (pintype "passive"))
    )
    (net (code "5") (name "BT_NDIS") (class "Default")
      (node (ref "JP3") (pin "3") (pinfunction "3_3") (pintype "bidirectional"))
      (node (ref "PI1") (pin "92") (pinfunction "92_92") (pintype "passive"))
    )
    (net (code "6") (name "CAM_GPIO0") (class "Default")
      (node (ref "J3") (pin "17") (pinfunction "17_17") (pintype "passive"))
      (node (ref "PI1") (pin "98") (pinfunction "98_98") (pintype "passive"))
    )
    (net (code "7") (name "CAM_GPIO1") (class "Default")
      (node (ref "J3") (pin "18") (pinfunction "18_18") (pintype "passive"))
      (node (ref "PI1") (pin "99") (pinfunction "99_99") (pintype "passive"))
    )
    (net (code "8") (name "CC1") (class "Default")
      (node (ref "PI1") (pin "93") (pinfunction "93_93") (pintype "passive"))
      (node (ref "USBC") (pin "A5") (pinfunction "CC1_A5") (pintype "passive"))
    )
    (net (code "9") (name "CC2") (class "Default")
      (node (ref "PI1") (pin "95") (pinfunction "95_95") (pintype "passive"))
      (node (ref "USBC") (pin "B5") (pinfunction "CC2_B5") (pintype "passive"))
    )
    (net (code "10") (name "DAC_~{CLR}") (class "Default")
      (node (ref "CON2") (pin "17") (pinfunction "17_17") (pintype "bidirectional"))
      (node (ref "MODULE_AIO") (pin "B13") (pinfunction "13_B13") (pintype "passive"))
    )
    (net (code "11") (name "DAC_~{LDAC}") (class "Default")
      (node (ref "CON2") (pin "19") (pinfunction "19_19") (pintype "bidirectional"))
      (node (ref "MODULE_AIO") (pin "B12") (pinfunction "12_B12") (pintype "passive"))
    )
    (net (code "12") (name "DIO_EN") (class "Default")
      (node (ref "CON3") (pin "29") (pinfunction "29_29") (pintype "bidirectional"))
      (node (ref "MODULE_DIO") (pin "A11") (pinfunction "11_A11") (pintype "passive"))
    )
    (net (code "13") (name "DIO_LEVEL_SELECT") (class "Default")
      (node (ref "CON3") (pin "25") (pinfunction "25_25") (pintype "bidirectional"))
      (node (ref "MODULE_DIO") (pin "A13") (pinfunction "13_A13") (pintype "passive"))
    )
    (net (code "14") (name "DIO_RESET") (class "Default")
      (node (ref "CON3") (pin "27") (pinfunction "27_27") (pintype "bidirectional"))
      (node (ref "MODULE_DIO") (pin "A12") (pinfunction "12_A12") (pintype "passive"))
    )
    (net (code "15") (name "DPHY0_DSIC_N") (class "Default")
      (node (ref "J3") (pin "8") (pinfunction "8_8") (pintype "passive"))
      (node (ref "PI1") (pin "128") (pinfunction "28_128") (pintype "passive"))
    )
    (net (code "16") (name "DPHY0_DSIC_P") (class "Default")
      (node (ref "J3") (pin "9") (pinfunction "9_9") (pintype "passive"))
      (node (ref "PI1") (pin "130") (pinfunction "30_130") (pintype "passive"))
    )
    (net (code "17") (name "DPHY0_DSID0_N") (class "Default")
      (node (ref "J3") (pin "2") (pinfunction "2_2") (pintype "passive"))
      (node (ref "PI1") (pin "116") (pinfunction "16_116") (pintype "passive"))
    )
    (net (code "18") (name "DPHY0_DSID0_P") (class "Default")
      (node (ref "J3") (pin "3") (pinfunction "3_3") (pintype "passive"))
      (node (ref "PI1") (pin "118") (pinfunction "18_118") (pintype "passive"))
    )
    (net (code "19") (name "DPHY0_DSID1_N") (class "Default")
      (node (ref "J3") (pin "5") (pinfunction "5_5") (pintype "passive"))
      (node (ref "PI1") (pin "122") (pinfunction "22_122") (pintype "passive"))
    )
    (net (code "20") (name "DPHY0_DSID1_P") (class "Default")
      (node (ref "J3") (pin "6") (pinfunction "6_6") (pintype "passive"))
      (node (ref "PI1") (pin "124") (pinfunction "24_124") (pintype "passive"))
    )
    (net (code "21") (name "DPHY0_DSID2_N") (class "Default")
      (node (ref "J3") (pin "11") (pinfunction "11_11") (pintype "passive"))
      (node (ref "PI1") (pin "134") (pinfunction "34_134") (pintype "passive"))
    )
    (net (code "22") (name "DPHY0_DSID2_P") (class "Default")
      (node (ref "J3") (pin "12") (pinfunction "12_12") (pintype "passive"))
      (node (ref "PI1") (pin "136") (pinfunction "36_136") (pintype "passive"))
    )
    (net (code "23") (name "DPHY0_DSID3_N") (class "Default")
      (node (ref "J3") (pin "14") (pinfunction "14_14") (pintype "passive"))
      (node (ref "PI1") (pin "140") (pinfunction "40_140") (pintype "passive"))
    )
    (net (code "24") (name "DPHY0_DSID3_P") (class "Default")
      (node (ref "J3") (pin "15") (pinfunction "15_15") (pintype "passive"))
      (node (ref "PI1") (pin "142") (pinfunction "42_142") (pintype "passive"))
    )
    (net (code "25") (name "DPHY1_DSIC_N") (class "Default")
      (node (ref "J4") (pin "8") (pinfunction "8_8") (pintype "passive"))
      (node (ref "PI1") (pin "188") (pinfunction "88_188") (pintype "passive"))
    )
    (net (code "26") (name "DPHY1_DSIC_P") (class "Default")
      (node (ref "J4") (pin "9") (pinfunction "9_9") (pintype "passive"))
      (node (ref "PI1") (pin "190") (pinfunction "90_190") (pintype "passive"))
    )
    (net (code "27") (name "DPHY1_DSID0_N") (class "Default")
      (node (ref "J4") (pin "2") (pinfunction "2_2") (pintype "passive"))
      (node (ref "PI1") (pin "176") (pinfunction "76_176") (pintype "passive"))
    )
    (net (code "28") (name "DPHY1_DSID0_P") (class "Default")
      (node (ref "J4") (pin "3") (pinfunction "3_3") (pintype "passive"))
      (node (ref "PI1") (pin "178") (pinfunction "78_178") (pintype "passive"))
    )
    (net (code "29") (name "DPHY1_DSID1_N") (class "Default")
      (node (ref "J4") (pin "5") (pinfunction "5_5") (pintype "passive"))
      (node (ref "PI1") (pin "182") (pinfunction "82_182") (pintype "passive"))
    )
    (net (code "30") (name "DPHY1_DSID1_P") (class "Default")
      (node (ref "J4") (pin "6") (pinfunction "6_6") (pintype "passive"))
      (node (ref "PI1") (pin "184") (pinfunction "84_184") (pintype "passive"))
    )
    (net (code "31") (name "DPHY1_DSID2_N") (class "Default")
      (node (ref "J4") (pin "11") (pinfunction "11_11") (pintype "passive"))
      (node (ref "PI1") (pin "194") (pinfunction "94_194") (pintype "passive"))
    )
    (net (code "32") (name "DPHY1_DSID2_P") (class "Default")
      (node (ref "J4") (pin "12") (pinfunction "12_12") (pintype "passive"))
      (node (ref "PI1") (pin "196") (pinfunction "96_196") (pintype "passive"))
    )
    (net (code "33") (name "DPHY1_DSID3_N") (class "Default")
      (node (ref "J4") (pin "14") (pinfunction "14_14") (pintype "passive"))
      (node (ref "PI1") (pin "193") (pinfunction "93_193") (pintype "passive"))
    )
    (net (code "34") (name "DPHY1_DSID3_P") (class "Default")
      (node (ref "J4") (pin "15") (pinfunction "15_15") (pintype "passive"))
      (node (ref "PI1") (pin "195") (pinfunction "95_195") (pintype "passive"))
    )
    (net (code "35") (name "EEPROM_NWP") (class "Default")
      (node (ref "JP2") (pin "4") (pinfunction "4_4") (pintype "bidirectional"))
      (node (ref "PI1") (pin "19") (pinfunction "19_19") (pintype "passive"))
    )
    (net (code "36") (name "ETH_LEDG") (class "Default")
      (node (ref "PI1") (pin "18") (pinfunction "18_18") (pintype "passive"))
      (node (ref "R8") (pin "1") (pinfunction "1_1") (pintype "passive"))
    )
    (net (code "37") (name "ETH_LEDY") (class "Default")
      (node (ref "PI1") (pin "16") (pinfunction "16_16") (pintype "passive"))
      (node (ref "R9") (pin "2") (pinfunction "2_2") (pintype "passive"))
    )
    (net (code "38") (name "ETH_TX1_N") (class "Default")
      (node (ref "D2") (pin "2") (pinfunction "D1-_2") (pintype "bidirectional"))
      (node (ref "D2") (pin "9") (pinfunction "D1-_9") (pintype "bidirectional"))
      (node (ref "ETH1") (pin "TD1-") (pinfunction "TD1-_TD1-") (pintype "bidirectional"))
      (node (ref "PI1") (pin "9") (pinfunction "9_9") (pintype "passive"))
    )
    (net (code "39") (name "ETH_TX1_P") (class "Default")
      (node (ref "D2") (pin "1") (pinfunction "D1+_1") (pintype "bidirectional"))
      (node (ref "D2") (pin "10") (pinfunction "D1+_10") (pintype "bidirectional"))
      (node (ref "ETH1") (pin "TD1+") (pinfunction "TD1+_TD1+") (pintype "bidirectional"))
      (node (ref "PI1") (pin "11") (pinfunction "11_11") (pintype "passive"))
    )
    (net (code "40") (name "ETH_TX2_N") (class "Default")
      (node (ref "D2") (pin "4") (pinfunction "D2+_4") (pintype "bidirectional"))
      (node (ref "D2") (pin "7") (pinfunction "D2+_7") (pintype "bidirectional"))
      (node (ref "ETH1") (pin "TD2-") (pinfunction "TD2-_TD2-") (pintype "bidirectional"))
      (node (ref "PI1") (pin "5") (pinfunction "5_5") (pintype "passive"))
    )
    (net (code "41") (name "ETH_TX2_P") (class "Default")
      (node (ref "D2") (pin "5") (pinfunction "D2-_5") (pintype "bidirectional"))
      (node (ref "D2") (pin "6") (pinfunction "D2-_6") (pintype "bidirectional"))
      (node (ref "ETH1") (pin "TD2+") (pinfunction "TD2+_TD2+") (pintype "bidirectional"))
      (node (ref "PI1") (pin "3") (pinfunction "3_3") (pintype "passive"))
    )
    (net (code "42") (name "ETH_TX3_N") (class "Default")
      (node (ref "D1") (pin "4") (pinfunction "D2+_4") (pintype "bidirectional"))
      (node (ref "D1") (pin "7") (pinfunction "D2+_7") (pintype "bidirectional"))
      (node (ref "ETH1") (pin "TD3-") (pinfunction "TD3-_TD3-") (pintype "bidirectional"))
      (node (ref "PI1") (pin "10") (pinfunction "10_10") (pintype "passive"))
    )
    (net (code "43") (name "ETH_TX3_P") (class "Default")
      (node (ref "D1") (pin "5") (pinfunction "D2-_5") (pintype "bidirectional"))
      (node (ref "D1") (pin "6") (pinfunction "D2-_6") (pintype "bidirectional"))
      (node (ref "ETH1") (pin "TD3+") (pinfunction "TD3+_TD3+") (pintype "bidirectional"))
      (node (ref "PI1") (pin "12") (pinfunction "12_12") (pintype "passive"))
    )
    (net (code "44") (name "ETH_TX4_N") (class "Default")
      (node (ref "D1") (pin "2") (pinfunction "D1-_2") (pintype "bidirectional"))
      (node (ref "D1") (pin "9") (pinfunction "D1-_9") (pintype "bidirectional"))
      (node (ref "ETH1") (pin "TD4-") (pinfunction "TD4-_TD4-") (pintype "bidirectional"))
      (node (ref "PI1") (pin "6") (pinfunction "6_6") (pintype "passive"))
    )
    (net (code "45") (name "ETH_TX4_P") (class "Default")
      (node (ref "D1") (pin "1") (pinfunction "D1+_1") (pintype "bidirectional"))
      (node (ref "D1") (pin "10") (pinfunction "D1+_10") (pintype "bidirectional"))
      (node (ref "ETH1") (pin "TD4+") (pinfunction "TD4+_TD4+") (pintype "bidirectional"))
      (node (ref "PI1") (pin "4") (pinfunction "4_4") (pintype "passive"))
    )
    (net (code "46") (name "GND") (class "Default")
      (node (ref "2230") (pin "1") (pinfunction "1_1") (pintype "passive"))
      (node (ref "2242") (pin "1") (pinfunction "1_1") (pintype "passive"))
      (node (ref "2260") (pin "1") (pinfunction "1_1") (pintype "passive"))
      (node (ref "2280") (pin "1") (pinfunction "1_1") (pintype "passive"))
      (node (ref "C1") (pin "2") (pinfunction "2_2") (pintype "passive"))
      (node (ref "C10") (pin "2") (pinfunction "2_2") (pintype "passive"))
      (node (ref "C11") (pin "2") (pinfunction "2_2") (pintype "passive"))
      (node (ref "C12") (pin "2") (pinfunction "2_2") (pintype "passive"))
      (node (ref "C14") (pin "2") (pinfunction "2_2") (pintype "passive"))
      (node (ref "C15") (pin "2") (pinfunction "2_2") (pintype "passive"))
      (node (ref "C16") (pin "2") (pinfunction "2_2") (pintype "passive"))
      (node (ref "C17") (pin "2") (pinfunction "2_2") (pintype "passive"))
      (node (ref "C18") (pin "2") (pinfunction "2_2") (pintype "passive"))
      (node (ref "C19") (pin "2") (pinfunction "2_2") (pintype "passive"))
      (node (ref "C2") (pin "2") (pinfunction "2_2") (pintype "passive"))
      (node (ref "C20") (pin "2") (pinfunction "2_2") (pintype "passive"))
      (node (ref "C21") (pin "2") (pinfunction "2_2") (pintype "passive"))
      (node (ref "C3") (pin "2") (pinfunction "2_2") (pintype "passive"))
      (node (ref "C4") (pin "2") (pinfunction "2_2") (pintype "passive"))
      (node (ref "C5") (pin "2") (pinfunction "2_2") (pintype "passive"))
      (node (ref "C6") (pin "2") (pinfunction "2_2") (pintype "passive"))
      (node (ref "C7") (pin "2") (pinfunction "2_2") (pintype "passive"))
      (node (ref "C8") (pin "2") (pinfunction "2_2") (pintype "passive"))
      (node (ref "C9") (pin "2") (pinfunction "2_2") (pintype "passive"))
      (node (ref "D1") (pin "3") (pinfunction "GND_3") (pintype "bidirectional"))
      (node (ref "D1") (pin "8") (pinfunction "GND_8") (pintype "bidirectional"))
      (node (ref "D2") (pin "3") (pinfunction "GND_3") (pintype "bidirectional"))
      (node (ref "D2") (pin "8") (pinfunction "GND_8") (pintype "bidirectional"))
      (node (ref "ETH1") (pin "MH3") (pinfunction "SHIELD_MH3") (pintype "bidirectional"))
      (node (ref "ETH1") (pin "MH4") (pinfunction "SHIELD_MH4") (pintype "bidirectional"))
      (node (ref "FAN") (pin "2") (pinfunction "P$2_2") (pintype "bidirectional"))
      (node (ref "GPIO") (pin "14") (pinfunction "14_14") (pintype "bidirectional"))
      (node (ref "GPIO") (pin "20") (pinfunction "20_20") (pintype "bidirectional"))
      (node (ref "GPIO") (pin "25") (pinfunction "25_25") (pintype "bidirectional"))
      (node (ref "GPIO") (pin "30") (pinfunction "30_30") (pintype "bidirectional"))
      (node (ref "GPIO") (pin "34") (pinfunction "34_34") (pintype "bidirectional"))
      (node (ref "GPIO") (pin "39") (pinfunction "39_39") (pintype "bidirectional"))
      (node (ref "GPIO") (pin "6") (pinfunction "6_6") (pintype "bidirectional"))
      (node (ref "GPIO") (pin "9") (pinfunction "9_9") (pintype "bidirectional"))
      (node (ref "HDMI1") (pin "11") (pinfunction "TMDSCLOCK+_11") (pintype "passive"))
      (node (ref "HDMI1") (pin "17") (pinfunction "UTILITY/HEAC+_17") (pintype "passive"))
      (node (ref "HDMI1") (pin "2") (pinfunction "TMDS2+_2") (pintype "passive"))
      (node (ref "HDMI1") (pin "5") (pinfunction "TMDSDATA1+_5") (pintype "passive"))
      (node (ref "HDMI1") (pin "8") (pinfunction "TMDS0+_8") (pintype "passive"))
      (node (ref "HDMI1") (pin "S1") (pinfunction "SHIELD_S1") (pintype "passive"))
      (node (ref "HDMI1") (pin "S2") (pinfunction "SHIELD_S2") (pintype "passive"))
      (node (ref "HDMI1") (pin "S3") (pinfunction "SHIELD_S3") (pintype "passive"))
      (node (ref "HDMI1") (pin "S4") (pinfunction "SHIELD_S4") (pintype "passive"))
      (node (ref "HDMI2") (pin "11") (pinfunction "TMDSCLOCK+_11") (pintype "passive"))
      (node (ref "HDMI2") (pin "17") (pinfunction "UTILITY/HEAC+_17") (pintype "passive"))
      (node (ref "HDMI2") (pin "2") (pinfunction "TMDS2+_2") (pintype "passive"))
      (node (ref "HDMI2") (pin "5") (pinfunction "TMDSDATA1+_5") (pintype "passive"))
      (node (ref "HDMI2") (pin "8") (pinfunction "TMDS0+_8") (pintype "passive"))
      (node (ref "HDMI2") (pin "S1") (pinfunction "SHIELD_S1") (pintype "passive"))
      (node (ref "HDMI2") (pin "S2") (pinfunction "SHIELD_S2") (pintype "passive"))
      (node (ref "HDMI2") (pin "S3") (pinfunction "SHIELD_S3") (pintype "passive"))
      (node (ref "HDMI2") (pin "S4") (pinfunction "SHIELD_S4") (pintype "passive"))
      (node (ref "IC1") (pin "2") (pinfunction "GND_2") (pintype "power_in"))
      (node (ref "IC2") (pin "2") (pinfunction "GND_2") (pintype "bidirectional"))
      (node (ref "IC3") (pin "3") (pinfunction "GND_3") (pintype "bidirectional"))
      (node (ref "IC4") (pin "3") (pinfunction "GND_3") (pintype "power_in"))
      (node (ref "IC5") (pin "4") (pinfunction "PGND_4") (pintype "power_in"))
      (node (ref "IC5") (pin "8") (pinfunction "SGND_8") (pintype "power_in"))
      (node (ref "IC5") (pin "9") (pinfunction "PGND_9") (pintype "power_in"))
      (node (ref "J1") (pin "4") (pinfunction "GND_4") (pintype "passive"))
      (node (ref "J1") (pin "7") (pinfunction "GND_DRAIN_7") (pintype "passive"))
      (node (ref "J1") (pin "S1") (pinfunction "SHIELD_S1") (pintype "passive"))
      (node (ref "J1") (pin "S2") (pinfunction "SHIELD_S2") (pintype "passive"))
      (node (ref "J2") (pin "4") (pinfunction "GND_4") (pintype "passive"))
      (node (ref "J2") (pin "7") (pinfunction "GND_DRAIN_7") (pintype "passive"))
      (node (ref "J2") (pin "S1") (pinfunction "SHIELD_S1") (pintype "passive"))
      (node (ref "J2") (pin "S2") (pinfunction "SHIELD_S2") (pintype "passive"))
      (node (ref "J3") (pin "1") (pinfunction "1_1") (pintype "passive"))
      (node (ref "J3") (pin "10") (pinfunction "10_10") (pintype "passive"))
      (node (ref "J3") (pin "13") (pinfunction "13_13") (pintype "passive"))
      (node (ref "J3") (pin "16") (pinfunction "16_16") (pintype "passive"))
      (node (ref "J3") (pin "19") (pinfunction "19_19") (pintype "passive"))
      (node (ref "J3") (pin "23") (pinfunction "MH1_23") (pintype "passive"))
      (node (ref "J3") (pin "24") (pinfunction "MH2_24") (pintype "passive"))
      (node (ref "J3") (pin "25") (pinfunction "MH1_25") (pintype "passive"))
      (node (ref "J3") (pin "26") (pinfunction "MH2_26") (pintype "passive"))
      (node (ref "J3") (pin "4") (pinfunction "4_4") (pintype "passive"))
      (node (ref "J3") (pin "7") (pinfunction "7_7") (pintype "passive"))
      (node (ref "J4") (pin "1") (pinfunction "1_1") (pintype "passive"))
      (node (ref "J4") (pin "10") (pinfunction "10_10") (pintype "passive"))
      (node (ref "J4") (pin "13") (pinfunction "13_13") (pintype "passive"))
      (node (ref "J4") (pin "16") (pinfunction "16_16") (pintype "passive"))
      (node (ref "J4") (pin "19") (pinfunction "19_19") (pintype "passive"))
      (node (ref "J4") (pin "23") (pinfunction "MH1_23") (pintype "passive"))
      (node (ref "J4") (pin "24") (pinfunction "MH2_24") (pintype "passive"))
      (node (ref "J4") (pin "25") (pinfunction "MH1_25") (pintype "passive"))
      (node (ref "J4") (pin "26") (pinfunction "MH2_26") (pintype "passive"))
      (node (ref "J4") (pin "4") (pinfunction "4_4") (pintype "passive"))
      (node (ref "J4") (pin "7") (pinfunction "7_7") (pintype "passive"))
      (node (ref "JP2") (pin "1") (pinfunction "1_1") (pintype "bidirectional"))
      (node (ref "JP2") (pin "11") (pinfunction "11_11") (pintype "bidirectional"))
      (node (ref "JP2") (pin "13") (pinfunction "13_13") (pintype "bidirectional"))
      (node (ref "JP2") (pin "3") (pinfunction "3_3") (pintype "bidirectional"))
      (node (ref "JP2") (pin "5") (pinfunction "5_5") (pintype "bidirectional"))
      (node (ref "JP2") (pin "7") (pinfunction "7_7") (pintype "bidirectional"))
      (node (ref "JP2") (pin "9") (pinfunction "9_9") (pintype "bidirectional"))
      (node (ref "JP3") (pin "2") (pinfunction "2_2") (pintype "bidirectional"))
      (node (ref "JP3") (pin "4") (pinfunction "4_4") (pintype "bidirectional"))
      (node (ref "MODULE_AIO") (pin "A10") (pinfunction "10_A10") (pintype "passive"))
      (node (ref "MODULE_AIO") (pin "A14") (pinfunction "14_A14") (pintype "passive"))
      (node (ref "MODULE_AIO") (pin "A15") (pinfunction "15_A15") (pintype "passive"))
      (node (ref "MODULE_AIO") (pin "A16") (pinfunction "16_A16") (pintype "passive"))
      (node (ref "MODULE_AIO") (pin "A25") (pinfunction "25_A25") (pintype "passive"))
      (node (ref "MODULE_AIO") (pin "A30") (pinfunction "30_A30") (pintype "passive"))
      (node (ref "MODULE_AIO") (pin "A31") (pinfunction "31_A31") (pintype "passive"))
      (node (ref "MODULE_AIO") (pin "A32") (pinfunction "32_A32") (pintype "passive"))
      (node (ref "MODULE_AIO") (pin "B10") (pinfunction "10_B10") (pintype "passive"))
      (node (ref "MODULE_AIO") (pin "B14") (pinfunction "14_B14") (pintype "passive"))
      (node (ref "MODULE_AIO") (pin "B15") (pinfunction "15_B15") (pintype "passive"))
      (node (ref "MODULE_AIO") (pin "B16") (pinfunction "16_B16") (pintype "passive"))
      (node (ref "MODULE_AIO") (pin "B19") (pinfunction "19_B19") (pintype "passive"))
      (node (ref "MODULE_AIO") (pin "B22") (pinfunction "22_B22") (pintype "passive"))
      (node (ref "MODULE_AIO") (pin "B25") (pinfunction "25_B25") (pintype "passive"))
      (node (ref "MODULE_AIO") (pin "B30") (pinfunction "30_B30") (pintype "passive"))
      (node (ref "MODULE_AIO") (pin "B31") (pinfunction "31_B31") (pintype "passive"))
      (node (ref "MODULE_AIO") (pin "B32") (pinfunction "32_B32") (pintype "passive"))
      (node (ref "MODULE_DIO") (pin "A10") (pinfunction "10_A10") (pintype "passive"))
      (node (ref "MODULE_DIO") (pin "A14") (pinfunction "14_A14") (pintype "passive"))
      (node (ref "MODULE_DIO") (pin "A15") (pinfunction "15_A15") (pintype "passive"))
      (node (ref "MODULE_DIO") (pin "A16") (pinfunction "16_A16") (pintype "passive"))
      (node (ref "MODULE_DIO") (pin "A25") (pinfunction "25_A25") (pintype "passive"))
      (node (ref "MODULE_DIO") (pin "A30") (pinfunction "30_A30") (pintype "passive"))
      (node (ref "MODULE_DIO") (pin "A31") (pinfunction "31_A31") (pintype "passive"))
      (node (ref "MODULE_DIO") (pin "A32") (pinfunction "32_A32") (pintype "passive"))
      (node (ref "MODULE_DIO") (pin "B10") (pinfunction "10_B10") (pintype "passive"))
      (node (ref "MODULE_DIO") (pin "B14") (pinfunction "14_B14") (pintype "passive"))
      (node (ref "MODULE_DIO") (pin "B15") (pinfunction "15_B15") (pintype "passive"))
      (node (ref "MODULE_DIO") (pin "B16") (pinfunction "16_B16") (pintype "passive"))
      (node (ref "MODULE_DIO") (pin "B19") (pinfunction "19_B19") (pintype "passive"))
      (node (ref "MODULE_DIO") (pin "B22") (pinfunction "22_B22") (pintype "passive"))
      (node (ref "MODULE_DIO") (pin "B25") (pinfunction "25_B25") (pintype "passive"))
      (node (ref "MODULE_DIO") (pin "B30") (pinfunction "30_B30") (pintype "passive"))
      (node (ref "MODULE_DIO") (pin "B31") (pinfunction "31_B31") (pintype "passive"))
      (node (ref "MODULE_DIO") (pin "B32") (pinfunction "32_B32") (pintype "passive"))
      (node (ref "PCIE") (pin "1") (pinfunction "GND1_1") (pintype "bidirectional"))
      (node (ref "PCIE") (pin "15") (pinfunction "GND4_15") (pintype "bidirectional"))
      (node (ref "PCIE") (pin "21") (pinfunction "GND5_21") (pintype "bidirectional"))
      (node (ref "PCIE") (pin "27") (pinfunction "GND6_27") (pintype "bidirectional"))
      (node (ref "PCIE") (pin "3") (pinfunction "GND2_3") (pintype "bidirectional"))
      (node (ref "PCIE") (pin "33") (pinfunction "GND7_33") (pintype "bidirectional"))
      (node (ref "PCIE") (pin "39") (pinfunction "GND8_39") (pintype "bidirectional"))
      (node (ref "PCIE") (pin "45") (pinfunction "GND9_45") (pintype "bidirectional"))
      (node (ref "PCIE") (pin "51") (pinfunction "GND10_51") (pintype "bidirectional"))
      (node (ref "PCIE") (pin "57") (pinfunction "GND11_57") (pintype "bidirectional"))
      (node (ref "PCIE") (pin "71") (pinfunction "GND12_71") (pintype "bidirectional"))
      (node (ref "PCIE") (pin "73") (pinfunction "GND13_73") (pintype "bidirectional"))
      (node (ref "PCIE") (pin "75") (pinfunction "GND14_75") (pintype "bidirectional"))
      (node (ref "PCIE") (pin "9") (pinfunction "GND3_9") (pintype "bidirectional"))
      (node (ref "PCIE") (pin "S1") (pinfunction "S1_S1") (pintype "bidirectional"))
      (node (ref "PCIE") (pin "S2") (pinfunction "S2_S2") (pintype "bidirectional"))
      (node (ref "PI1") (pin "1") (pinfunction "1_1") (pintype "passive"))
      (node (ref "PI1") (pin "107") (pinfunction "7_107") (pintype "passive"))
      (node (ref "PI1") (pin "108") (pinfunction "8_108") (pintype "passive"))
      (node (ref "PI1") (pin "113") (pinfunction "13_113") (pintype "passive"))
      (node (ref "PI1") (pin "114") (pinfunction "14_114") (pintype "passive"))
      (node (ref "PI1") (pin "119") (pinfunction "19_119") (pintype "passive"))
      (node (ref "PI1") (pin "120") (pinfunction "20_120") (pintype "passive"))
      (node (ref "PI1") (pin "125") (pinfunction "25_125") (pintype "passive"))
      (node (ref "PI1") (pin "126") (pinfunction "26_126") (pintype "passive"))
      (node (ref "PI1") (pin "13") (pinfunction "13_13") (pintype "passive"))
      (node (ref "PI1") (pin "131") (pinfunction "31_131") (pintype "passive"))
      (node (ref "PI1") (pin "132") (pinfunction "32_132") (pintype "passive"))
      (node (ref "PI1") (pin "137") (pinfunction "37_137") (pintype "passive"))
      (node (ref "PI1") (pin "138") (pinfunction "38_138") (pintype "passive"))
      (node (ref "PI1") (pin "14") (pinfunction "14_14") (pintype "passive"))
      (node (ref "PI1") (pin "143") (pinfunction "43_143") (pintype "passive"))
      (node (ref "PI1") (pin "149") (pinfunction "49_149") (pintype "passive"))
      (node (ref "PI1") (pin "155") (pinfunction "55_155") (pintype "passive"))
      (node (ref "PI1") (pin "156") (pinfunction "56_156") (pintype "passive"))
      (node (ref "PI1") (pin "161") (pinfunction "61_161") (pintype "passive"))
      (node (ref "PI1") (pin "162") (pinfunction "62_162") (pintype "passive"))
      (node (ref "PI1") (pin "167") (pinfunction "67_167") (pintype "passive"))
      (node (ref "PI1") (pin "168") (pinfunction "68_168") (pintype "passive"))
      (node (ref "PI1") (pin "173") (pinfunction "73_173") (pintype "passive"))
      (node (ref "PI1") (pin "174") (pinfunction "74_174") (pintype "passive"))
      (node (ref "PI1") (pin "179") (pinfunction "79_179") (pintype "passive"))
      (node (ref "PI1") (pin "180") (pinfunction "80_180") (pintype "passive"))
      (node (ref "PI1") (pin "185") (pinfunction "85_185") (pintype "passive"))
      (node (ref "PI1") (pin "186") (pinfunction "86_186") (pintype "passive"))
      (node (ref "PI1") (pin "191") (pinfunction "91_191") (pintype "passive"))
      (node (ref "PI1") (pin "192") (pinfunction "92_192") (pintype "passive"))
      (node (ref "PI1") (pin "197") (pinfunction "97_197") (pintype "passive"))
      (node (ref "PI1") (pin "198") (pinfunction "98_198") (pintype "passive"))
      (node (ref "PI1") (pin "2") (pinfunction "2_2") (pintype "passive"))
      (node (ref "PI1") (pin "21") (pinfunction "21_21") (pintype "passive"))
      (node (ref "PI1") (pin "24") (pinfunction "24_24") (pintype "passive"))
      (node (ref "PI1") (pin "31") (pinfunction "31_31") (pintype "passive"))
      (node (ref "PI1") (pin "34") (pinfunction "34_34") (pintype "passive"))
      (node (ref "PI1") (pin "41") (pinfunction "41_41") (pintype "passive"))
      (node (ref "PI1") (pin "44") (pinfunction "44_44") (pintype "passive"))
      (node (ref "PI1") (pin "51") (pinfunction "51_51") (pintype "passive"))
      (node (ref "PI1") (pin "54") (pinfunction "54_54") (pintype "passive"))
      (node (ref "PI1") (pin "59") (pinfunction "59_59") (pintype "passive"))
      (node (ref "PI1") (pin "60") (pinfunction "60_60") (pintype "passive"))
      (node (ref "PI1") (pin "65") (pinfunction "65_65") (pintype "passive"))
      (node (ref "PI1") (pin "66") (pinfunction "66_66") (pintype "passive"))
      (node (ref "PI1") (pin "7") (pinfunction "7_7") (pintype "passive"))
      (node (ref "PI1") (pin "72") (pinfunction "72_72") (pintype "passive"))
      (node (ref "PI1") (pin "73") (pinfunction "73_73") (pintype "passive"))
      (node (ref "PI1") (pin "8") (pinfunction "8_8") (pintype "passive"))
      (node (ref "PI1") (pin "97") (pinfunction "97_97") (pintype "passive"))
      (node (ref "R1") (pin "2") (pinfunction "2_2") (pintype "passive"))
      (node (ref "R11") (pin "2") (pinfunction "2_2") (pintype "passive"))
      (node (ref "R13") (pin "2") (pinfunction "2_2") (pintype "passive"))
      (node (ref "R2") (pin "2") (pinfunction "2_2") (pintype "passive"))
      (node (ref "SD1") (pin "MT1") (pinfunction "MT1_MT1") (pintype "bidirectional"))
      (node (ref "SD1") (pin "MT2") (pinfunction "MT2_MT2") (pintype "bidirectional"))
      (node (ref "SD1") (pin "MT3") (pinfunction "MT3_MT3") (pintype "bidirectional"))
      (node (ref "SD1") (pin "MT4") (pinfunction "MT4_MT4") (pintype "bidirectional"))
      (node (ref "SD1") (pin "VSS") (pinfunction "VSS_VSS") (pintype "bidirectional"))
      (node (ref "SW1") (pin "1") (pinfunction "1_1") (pintype "passive"))
      (node (ref "SW1") (pin "3") (pinfunction "3_3") (pintype "passive"))
      (node (ref "SW1") (pin "4") (pinfunction "4_4") (pintype "passive"))
      (node (ref "USBC") (pin "A1") (pinfunction "GND_A1") (pintype "passive"))
      (node (ref "USBC") (pin "A12") (pinfunction "GND1_A12") (pintype "passive"))
      (node (ref "USBC") (pin "B1") (pinfunction "GND3_B1") (pintype "passive"))
      (node (ref "USBC") (pin "B12") (pinfunction "GND2_B12") (pintype "passive"))
      (node (ref "USBC") (pin "S1") (pinfunction "SHIELD_S1") (pintype "passive"))
      (node (ref "USBC") (pin "S2") (pinfunction "SHIELD_S2") (pintype "passive"))
      (node (ref "USBC") (pin "S3") (pinfunction "SHIELD_S3") (pintype "passive"))
      (node (ref "USBC") (pin "S4") (pinfunction "SHIELD_S4") (pintype "passive"))
      (node (ref "X2") (pin "2") (pinfunction "VSS_2") (pintype "power_in"))
    )
    (net (code "47") (name "GPIO2") (class "Default")
      (node (ref "CON3") (pin "24") (pinfunction "24_24") (pintype "bidirectional"))
      (node (ref "GPIO") (pin "3") (pinfunction "3_3") (pintype "bidirectional"))
      (node (ref "PI1") (pin "57") (pinfunction "57_57") (pintype "passive"))
    )
    (net (code "48") (name "GPIO3") (class "Default")
      (node (ref "CON3") (pin "22") (pinfunction "22_22") (pintype "bidirectional"))
      (node (ref "GPIO") (pin "5") (pinfunction "5_5") (pintype "bidirectional"))
      (node (ref "PI1") (pin "55") (pinfunction "55_55") (pintype "passive"))
    )
    (net (code "49") (name "GPIO4") (class "Default")
      (node (ref "CON2") (pin "28") (pinfunction "28_28") (pintype "bidirectional"))
      (node (ref "GPIO") (pin "7") (pinfunction "7_7") (pintype "bidirectional"))
      (node (ref "PI1") (pin "53") (pinfunction "53_53") (pintype "passive"))
    )
    (net (code "50") (name "GPIO5") (class "Default")
      (node (ref "CON2") (pin "22") (pinfunction "22_22") (pintype "bidirectional"))
      (node (ref "GPIO") (pin "29") (pinfunction "29_29") (pintype "bidirectional"))
      (node (ref "PI1") (pin "33") (pinfunction "33_33") (pintype "passive"))
    )
    (net (code "51") (name "GPIO6") (class "Default")
      (node (ref "CON2") (pin "26") (pinfunction "26_26") (pintype "bidirectional"))
      (node (ref "CON3") (pin "30") (pinfunction "30_30") (pintype "bidirectional"))
      (node (ref "GPIO") (pin "31") (pinfunction "31_31") (pintype "bidirectional"))
      (node (ref "PI1") (pin "29") (pinfunction "29_29") (pintype "passive"))
    )
    (net (code "52") (name "GPIO7") (class "Default")
      (node (ref "CON3") (pin "4") (pinfunction "4_4") (pintype "bidirectional"))
      (node (ref "GPIO") (pin "26") (pinfunction "26_26") (pintype "bidirectional"))
      (node (ref "PI1") (pin "38") (pinfunction "38_38") (pintype "passive"))
    )
    (net (code "53") (name "GPIO8") (class "Default")
      (node (ref "CON3") (pin "6") (pinfunction "6_6") (pintype "bidirectional"))
      (node (ref "GPIO") (pin "24") (pinfunction "24_24") (pintype "bidirectional"))
      (node (ref "PI1") (pin "40") (pinfunction "40_40") (pintype "passive"))
    )
    (net (code "54") (name "GPIO9") (class "Default")
      (node (ref "CON3") (pin "12") (pinfunction "12_12") (pintype "bidirectional"))
      (node (ref "GPIO") (pin "21") (pinfunction "21_21") (pintype "bidirectional"))
      (node (ref "PI1") (pin "39") (pinfunction "39_39") (pintype "passive"))
    )
    (net (code "55") (name "GPIO10") (class "Default")
      (node (ref "CON3") (pin "10") (pinfunction "10_10") (pintype "bidirectional"))
      (node (ref "GPIO") (pin "19") (pinfunction "19_19") (pintype "bidirectional"))
      (node (ref "PI1") (pin "43") (pinfunction "43_43") (pintype "passive"))
    )
    (net (code "56") (name "GPIO11") (class "Default")
      (node (ref "CON3") (pin "8") (pinfunction "8_8") (pintype "bidirectional"))
      (node (ref "GPIO") (pin "23") (pinfunction "23_23") (pintype "bidirectional"))
      (node (ref "PI1") (pin "37") (pinfunction "37_37") (pintype "passive"))
    )
    (net (code "57") (name "GPIO12") (class "Default")
      (node (ref "CON2") (pin "18") (pinfunction "18_18") (pintype "bidirectional"))
      (node (ref "GPIO") (pin "32") (pinfunction "32_32") (pintype "bidirectional"))
      (node (ref "PI1") (pin "32") (pinfunction "32_32") (pintype "passive"))
    )
    (net (code "58") (name "GPIO13") (class "Default")
      (node (ref "CON2") (pin "24") (pinfunction "24_24") (pintype "bidirectional"))
      (node (ref "GPIO") (pin "33") (pinfunction "33_33") (pintype "bidirectional"))
      (node (ref "PI1") (pin "27") (pinfunction "27_27") (pintype "passive"))
    )
    (net (code "59") (name "GPIO14") (class "Default")
      (node (ref "CON3") (pin "18") (pinfunction "18_18") (pintype "bidirectional"))
      (node (ref "GPIO") (pin "8") (pinfunction "8_8") (pintype "bidirectional"))
      (node (ref "PI1") (pin "56") (pinfunction "56_56") (pintype "passive"))
    )
    (net (code "60") (name "GPIO15") (class "Default")
      (node (ref "CON3") (pin "20") (pinfunction "20_20") (pintype "bidirectional"))
      (node (ref "GPIO") (pin "10") (pinfunction "10_10") (pintype "bidirectional"))
      (node (ref "PI1") (pin "52") (pinfunction "52_52") (pintype "passive"))
    )
    (net (code "61") (name "GPIO16") (class "Default")
      (node (ref "CON2") (pin "36") (pinfunction "36_36") (pintype "bidirectional"))
      (node (ref "GPIO") (pin "36") (pinfunction "36_36") (pintype "bidirectional"))
      (node (ref "PI1") (pin "30") (pinfunction "30_30") (pintype "passive"))
    )
    (net (code "62") (name "GPIO17") (class "Default")
      (node (ref "CON2") (pin "38") (pinfunction "38_38") (pintype "bidirectional"))
      (node (ref "GPIO") (pin "11") (pinfunction "11_11") (pintype "bidirectional"))
      (node (ref "PI1") (pin "49") (pinfunction "49_49") (pintype "passive"))
    )
    (net (code "63") (name "GPIO18") (class "Default")
      (node (ref "CON2") (pin "40") (pinfunction "40_40") (pintype "bidirectional"))
      (node (ref "GPIO") (pin "12") (pinfunction "12_12") (pintype "bidirectional"))
      (node (ref "PI1") (pin "50") (pinfunction "50_50") (pintype "passive"))
    )
    (net (code "64") (name "GPIO19") (class "Default")
      (node (ref "CON2") (pin "30") (pinfunction "30_30") (pintype "bidirectional"))
      (node (ref "GPIO") (pin "35") (pinfunction "35_35") (pintype "bidirectional"))
      (node (ref "PI1") (pin "25") (pinfunction "25_25") (pintype "passive"))
    )
    (net (code "65") (name "GPIO20") (class "Default")
      (node (ref "CON2") (pin "32") (pinfunction "32_32") (pintype "bidirectional"))
      (node (ref "GPIO") (pin "38") (pinfunction "38_38") (pintype "bidirectional"))
      (node (ref "PI1") (pin "28") (pinfunction "28_28") (pintype "passive"))
    )
    (net (code "66") (name "GPIO21") (class "Default")
      (node (ref "CON2") (pin "34") (pinfunction "34_34") (pintype "bidirectional"))
      (node (ref "GPIO") (pin "40") (pinfunction "40_40") (pintype "bidirectional"))
      (node (ref "PI1") (pin "26") (pinfunction "26_26") (pintype "passive"))
    )
    (net (code "67") (name "GPIO22") (class "Default")
      (node (ref "CON3") (pin "32") (pinfunction "32_32") (pintype "bidirectional"))
      (node (ref "GPIO") (pin "15") (pinfunction "15_15") (pintype "bidirectional"))
      (node (ref "PI1") (pin "45") (pinfunction "45_45") (pintype "passive"))
    )
    (net (code "68") (name "GPIO23") (class "Default")
      (node (ref "GPIO") (pin "16") (pinfunction "16_16") (pintype "bidirectional"))
      (node (ref "PI1") (pin "48") (pinfunction "48_48") (pintype "passive"))
    )
    (net (code "69") (name "GPIO24") (class "Default")
      (node (ref "CON3") (pin "14") (pinfunction "14_14") (pintype "bidirectional"))
      (node (ref "GPIO") (pin "18") (pinfunction "18_18") (pintype "bidirectional"))
      (node (ref "PI1") (pin "46") (pinfunction "46_46") (pintype "passive"))
    )
    (net (code "70") (name "GPIO25") (class "Default")
      (node (ref "CON3") (pin "16") (pinfunction "16_16") (pintype "bidirectional"))
      (node (ref "GPIO") (pin "22") (pinfunction "22_22") (pintype "bidirectional"))
      (node (ref "PI1") (pin "42") (pinfunction "42_42") (pintype "passive"))
    )
    (net (code "71") (name "GPIO26") (class "Default")
      (node (ref "CON2") (pin "20") (pinfunction "20_20") (pintype "bidirectional"))
      (node (ref "GPIO") (pin "37") (pinfunction "37_37") (pintype "bidirectional"))
      (node (ref "PI1") (pin "23") (pinfunction "23_23") (pintype "passive"))
    )
    (net (code "72") (name "GPIO27") (class "Default")
      (node (ref "CON3") (pin "34") (pinfunction "34_34") (pintype "bidirectional"))
      (node (ref "GPIO") (pin "13") (pinfunction "13_13") (pintype "bidirectional"))
      (node (ref "PI1") (pin "47") (pinfunction "47_47") (pintype "passive"))
    )
    (net (code "73") (name "GPIO_VREF") (class "Default")
      (node (ref "PI1") (pin "77") (pinfunction "77_77") (pintype "passive"))
      (node (ref "R3") (pin "1") (pinfunction "1_1") (pintype "passive"))
      (node (ref "R4") (pin "1") (pinfunction "1_1") (pintype "passive"))
      (node (ref "R6") (pin "2") (pinfunction "2_2") (pintype "passive"))
      (node (ref "R7") (pin "2") (pinfunction "2_2") (pintype "passive"))
      (node (ref "TP-GREF") (pin "TP") (pinfunction "P$1_TP") (pintype "bidirectional"))
    )
    (net (code "74") (name "HDMI0_CEC") (class "Default")
      (node (ref "HDMI2") (pin "13") (pinfunction "GROUND_13") (pintype "passive"))
      (node (ref "PI1") (pin "152") (pinfunction "52_152") (pintype "passive"))
    )
    (net (code "75") (name "HDMI0_HOTPLUG") (class "Default")
      (node (ref "HDMI2") (pin "19") (pinfunction "HOTPLUG/HEC+_19") (pintype "passive"))
      (node (ref "PI1") (pin "154") (pinfunction "54_154") (pintype "passive"))
    )
    (net (code "76") (name "HDMI0_SCL") (class "Default")
      (node (ref "HDMI2") (pin "15") (pinfunction "SCL_15") (pintype "passive"))
      (node (ref "PI1") (pin "199") (pinfunction "99_199") (pintype "passive"))
    )
    (net (code "77") (name "HDMI0_SDA") (class "Default")
      (node (ref "HDMI2") (pin "16") (pinfunction "SDA_16") (pintype "passive"))
      (node (ref "PI1") (pin "200") (pinfunction "100_200") (pintype "passive"))
    )
    (net (code "78") (name "HDMI0_TDMS0_N") (class "Default")
      (node (ref "HDMI2") (pin "9") (pinfunction "TMDS0-_9") (pintype "passive"))
      (node (ref "PI1") (pin "183") (pinfunction "83_183") (pintype "passive"))
    )
    (net (code "79") (name "HDMI0_TDMS0_P") (class "Default")
      (node (ref "HDMI2") (pin "7") (pinfunction "TMDS0SHIELD_7") (pintype "passive"))
      (node (ref "PI1") (pin "181") (pinfunction "81_181") (pintype "passive"))
    )
    (net (code "80") (name "HDMI0_TDMS1_N") (class "Default")
      (node (ref "HDMI2") (pin "6") (pinfunction "TMDS1-_6") (pintype "passive"))
      (node (ref "PI1") (pin "177") (pinfunction "77_177") (pintype "passive"))
    )
    (net (code "81") (name "HDMI0_TDMS1_P") (class "Default")
      (node (ref "HDMI2") (pin "4") (pinfunction "TMDS1SHIELD_4") (pintype "passive"))
      (node (ref "PI1") (pin "175") (pinfunction "75_175") (pintype "passive"))
    )
    (net (code "82") (name "HDMI0_TDMS2_N") (class "Default")
      (node (ref "HDMI2") (pin "3") (pinfunction "TMDS2-_3") (pintype "passive"))
      (node (ref "PI1") (pin "171") (pinfunction "71_171") (pintype "passive"))
    )
    (net (code "83") (name "HDMI0_TDMS2_P") (class "Default")
      (node (ref "HDMI2") (pin "1") (pinfunction "TMDS2SHIELD_1") (pintype "passive"))
      (node (ref "PI1") (pin "169") (pinfunction "69_169") (pintype "passive"))
    )
    (net (code "84") (name "HDMI0_TDMSCK_N") (class "Default")
      (node (ref "HDMI2") (pin "12") (pinfunction "TMDSCLOCK-_12") (pintype "passive"))
      (node (ref "PI1") (pin "189") (pinfunction "89_189") (pintype "passive"))
    )
    (net (code "85") (name "HDMI0_TDMSCK_P") (class "Default")
      (node (ref "HDMI2") (pin "10") (pinfunction "TMDSCLOCKSHIELD_10") (pintype "passive"))
      (node (ref "PI1") (pin "187") (pinfunction "87_187") (pintype "passive"))
    )
    (net (code "86") (name "HDMI1_CEC") (class "Default")
      (node (ref "HDMI1") (pin "13") (pinfunction "GROUND_13") (pintype "passive"))
      (node (ref "PI1") (pin "150") (pinfunction "50_150") (pintype "passive"))
    )
    (net (code "87") (name "HDMI1_HOTPLUG") (class "Default")
      (node (ref "HDMI1") (pin "19") (pinfunction "HOTPLUG/HEC+_19") (pintype "passive"))
      (node (ref "PI1") (pin "144") (pinfunction "44_144") (pintype "passive"))
    )
    (net (code "88") (name "HDMI1_SCL") (class "Default")
      (node (ref "HDMI1") (pin "15") (pinfunction "SCL_15") (pintype "passive"))
      (node (ref "PI1") (pin "148") (pinfunction "48_148") (pintype "passive"))
    )
    (net (code "89") (name "HDMI1_SDA") (class "Default")
      (node (ref "HDMI1") (pin "16") (pinfunction "SDA_16") (pintype "passive"))
      (node (ref "PI1") (pin "146") (pinfunction "46_146") (pintype "passive"))
    )
    (net (code "90") (name "HDMI1_TDMS0_N") (class "Default")
      (node (ref "HDMI1") (pin "9") (pinfunction "TMDS0-_9") (pintype "passive"))
      (node (ref "PI1") (pin "159") (pinfunction "59_159") (pintype "passive"))
    )
    (net (code "91") (name "HDMI1_TDMS0_P") (class "Default")
      (node (ref "HDMI1") (pin "7") (pinfunction "TMDS0SHIELD_7") (pintype "passive"))
      (node (ref "PI1") (pin "157") (pinfunction "57_157") (pintype "passive"))
    )
    (net (code "92") (name "HDMI1_TDMS1_N") (class "Default")
      (node (ref "HDMI1") (pin "6") (pinfunction "TMDS1-_6") (pintype "passive"))
      (node (ref "PI1") (pin "153") (pinfunction "53_153") (pintype "passive"))
    )
    (net (code "93") (name "HDMI1_TDMS1_P") (class "Default")
      (node (ref "HDMI1") (pin "4") (pinfunction "TMDS1SHIELD_4") (pintype "passive"))
      (node (ref "PI1") (pin "151") (pinfunction "51_151") (pintype "passive"))
    )
    (net (code "94") (name "HDMI1_TDMS2_N") (class "Default")
      (node (ref "HDMI1") (pin "3") (pinfunction "TMDS2-_3") (pintype "passive"))
      (node (ref "PI1") (pin "147") (pinfunction "47_147") (pintype "passive"))
    )
    (net (code "95") (name "HDMI1_TDMS2_P") (class "Default")
      (node (ref "HDMI1") (pin "1") (pinfunction "TMDS2SHIELD_1") (pintype "passive"))
      (node (ref "PI1") (pin "145") (pinfunction "45_145") (pintype "passive"))
    )
    (net (code "96") (name "HDMI1_TDMSCK_N") (class "Default")
      (node (ref "HDMI1") (pin "12") (pinfunction "TMDSCLOCK-_12") (pintype "passive"))
      (node (ref "PI1") (pin "165") (pinfunction "65_165") (pintype "passive"))
    )
    (net (code "97") (name "HDMI1_TDMSCK_P") (class "Default")
      (node (ref "HDMI1") (pin "10") (pinfunction "TMDSCLOCKSHIELD_10") (pintype "passive"))
      (node (ref "PI1") (pin "163") (pinfunction "63_163") (pintype "passive"))
    )
    (net (code "98") (name "HDMI_5V") (class "Default")
      (node (ref "C4") (pin "1") (pinfunction "1_1") (pintype "passive"))
      (node (ref "HDMI1") (pin "18") (pinfunction "POWER_18") (pintype "power_in"))
      (node (ref "HDMI2") (pin "18") (pinfunction "POWER_18") (pintype "power_in"))
      (node (ref "IC4") (pin "2") (pinfunction "OUT_2") (pintype "power_in"))
      (node (ref "TP-5VHD") (pin "TP") (pinfunction "P$1_TP") (pintype "bidirectional"))
    )
    (net (code "99") (name "ID_SC") (class "Default")
      (node (ref "GPIO") (pin "28") (pinfunction "28_28") (pintype "bidirectional"))
      (node (ref "ID") (pin "1") (pinfunction "1_1") (pintype "bidirectional"))
      (node (ref "PI1") (pin "36") (pinfunction "36_36") (pintype "passive"))
    )
    (net (code "100") (name "ID_SD") (class "Default")
      (node (ref "GPIO") (pin "27") (pinfunction "27_27") (pintype "bidirectional"))
      (node (ref "ID") (pin "3") (pinfunction "3_3") (pintype "bidirectional"))
      (node (ref "PI1") (pin "35") (pinfunction "35_35") (pintype "passive"))
    )
    (net (code "101") (name "LED_NACT") (class "Default")
      (node (ref "PI1") (pin "22") (pinfunction "22_22") (pintype "passive"))
    )
    (net (code "102") (name "M2_3V3") (class "Default")
      (node (ref "C12") (pin "1") (pinfunction "1_1") (pintype "passive"))
      (node (ref "C13") (pin "1") (pinfunction "1_1") (pintype "passive"))
      (node (ref "C14") (pin "1") (pinfunction "1_1") (pintype "passive"))
      (node (ref "C15") (pin "1") (pinfunction "1_1") (pintype "passive"))
      (node (ref "C16") (pin "1") (pinfunction "1_1") (pintype "passive"))
      (node (ref "C17") (pin "1") (pinfunction "1_1") (pintype "passive"))
      (node (ref "L1") (pin "2") (pinfunction "2_2") (pintype "passive"))
      (node (ref "PCIE") (pin "12") (pinfunction "VCC3_12") (pintype "bidirectional"))
      (node (ref "PCIE") (pin "14") (pinfunction "VCC4_14") (pintype "bidirectional"))
      (node (ref "PCIE") (pin "16") (pinfunction "VCC5_16") (pintype "bidirectional"))
      (node (ref "PCIE") (pin "18") (pinfunction "VCC6_18") (pintype "bidirectional"))
      (node (ref "PCIE") (pin "2") (pinfunction "VCC1_2") (pintype "bidirectional"))
      (node (ref "PCIE") (pin "4") (pinfunction "VCC2_4") (pintype "bidirectional"))
      (node (ref "PCIE") (pin "70") (pinfunction "VCC7_70") (pintype "bidirectional"))
      (node (ref "PCIE") (pin "72") (pinfunction "VCC8_72") (pintype "bidirectional"))
      (node (ref "PCIE") (pin "74") (pinfunction "VCC9_74") (pintype "bidirectional"))
      (node (ref "R12") (pin "1") (pinfunction "1_1") (pintype "passive"))
      (node (ref "TP-VM2") (pin "TP") (pinfunction "P$1_TP") (pintype "bidirectional"))
      (node (ref "X2") (pin "3") (pinfunction "OUT_3") (pintype "output"))
      (node (ref "X2") (pin "4") (pinfunction "VDD_4") (pintype "power_in"))
    )
    (net (code "103") (name "MISO_SEL") (class "Default")
      (node (ref "CON2") (pin "23") (pinfunction "23_23") (pintype "bidirectional"))
      (node (ref "MODULE_AIO") (pin "A13") (pinfunction "13_A13") (pintype "passive"))
    )
    (net (code "104") (name "NPWR_LED") (class "Default")
      (node (ref "IC3") (pin "2") (pinfunction "A_2") (pintype "input"))
      (node (ref "PI1") (pin "96") (pinfunction "96_96") (pintype "passive"))
      (node (ref "TP-LED") (pin "TP") (pinfunction "P$1_TP") (pintype "bidirectional"))
    )
    (net (code "105") (name "NRPIBOOT") (class "Default")
      (node (ref "JP2") (pin "2") (pinfunction "2_2") (pintype "bidirectional"))
      (node (ref "PI1") (pin "94") (pinfunction "94_94") (pintype "passive"))
    )
    (net (code "106") (name "Net-(C11-Pad1)") (class "Default")
      (node (ref "C11") (pin "1") (pinfunction "1_1") (pintype "passive"))
      (node (ref "ETH1") (pin "CT1") (pinfunction "CT1_CT1") (pintype "bidirectional"))
      (node (ref "ETH1") (pin "CT2") (pinfunction "CT2_CT2") (pintype "bidirectional"))
      (node (ref "ETH1") (pin "CT3") (pinfunction "CT3_CT3") (pintype "bidirectional"))
      (node (ref "ETH1") (pin "CT4") (pinfunction "CT4_CT4") (pintype "bidirectional"))
    )
    (net (code "107") (name "Net-(ETH1-P17)") (class "Default")
      (node (ref "ETH1") (pin "17") (pinfunction "P17_17") (pintype "bidirectional"))
      (node (ref "R9") (pin "1") (pinfunction "1_1") (pintype "passive"))
    )
    (net (code "108") (name "Net-(ETH1-P19)") (class "Default")
      (node (ref "ETH1") (pin "19") (pinfunction "P19_19") (pintype "bidirectional"))
      (node (ref "R8") (pin "2") (pinfunction "2_2") (pintype "passive"))
    )
    (net (code "109") (name "Net-(IC2-ILIM)") (class "Default")
      (node (ref "IC2") (pin "5") (pinfunction "ILIM_5") (pintype "bidirectional"))
      (node (ref "R2") (pin "1") (pinfunction "1_1") (pintype "passive"))
    )
    (net (code "110") (name "Net-(IC3-Y)") (class "Default")
      (node (ref "IC3") (pin "4") (pinfunction "Y_4") (pintype "output"))
      (node (ref "R5") (pin "2") (pinfunction "2_2") (pintype "passive"))
    )
    (net (code "111") (name "Net-(IC5-FB)") (class "Default")
      (node (ref "C13") (pin "2") (pinfunction "2_2") (pintype "passive"))
      (node (ref "IC5") (pin "1") (pinfunction "FB_1") (pintype "bidirectional"))
      (node (ref "R12") (pin "2") (pinfunction "2_2") (pintype "passive"))
      (node (ref "R13") (pin "1") (pinfunction "1_1") (pintype "passive"))
      (node (ref "TP-M2FB") (pin "TP") (pinfunction "P$1_TP") (pintype "bidirectional"))
    )
    (net (code "112") (name "Net-(IC5-LX)") (class "Default")
      (node (ref "IC5") (pin "6") (pinfunction "LX_6") (pintype "power_in"))
      (node (ref "L1") (pin "1") (pinfunction "1_1") (pintype "passive"))
      (node (ref "TP-LX") (pin "TP") (pinfunction "P$1_TP") (pintype "bidirectional"))
    )
    (net (code "113") (name "Net-(J4-Pad17)") (class "Default")
      (node (ref "J4") (pin "17") (pinfunction "17_17") (pintype "passive"))
      (node (ref "R61") (pin "1") (pinfunction "1_1") (pintype "passive"))
    )
    (net (code "114") (name "Net-(LED1-PadC)") (class "Default")
      (node (ref "LED1") (pin "C") (pinfunction "C_C") (pintype "passive"))
      (node (ref "R5") (pin "1") (pinfunction "1_1") (pintype "passive"))
    )
    (net (code "115") (name "Net-(LED2-PadC)") (class "Default")
      (node (ref "LED2") (pin "C") (pinfunction "C_C") (pintype "passive"))
      (node (ref "R10") (pin "1") (pinfunction "1_1") (pintype "passive"))
    )
    (net (code "116") (name "Net-(PCIE-DA5{slash}~{DSS}{slash}~{LED1})") (class "Default")
      (node (ref "PCIE") (pin "10") (pinfunction "DA5/~{DSS}/~{LED1}_10") (pintype "bidirectional"))
      (node (ref "R10") (pin "2") (pinfunction "2_2") (pintype "passive"))
    )
    (net (code "117") (name "Net-(PCIE-SUSCLK)") (class "Default")
      (node (ref "PCIE") (pin "68") (pinfunction "SUSCLK_68") (pintype "bidirectional"))
      (node (ref "TP-M2CLK") (pin "TP") (pinfunction "P$1_TP") (pintype "bidirectional"))
      (node (ref "X2") (pin "1") (pinfunction "CON_1") (pintype "input"))
    )
    (net (code "118") (name "PCIE_CLK_N") (class "Default")
      (node (ref "PCIE") (pin "53") (pinfunction "REFCLK_N_53") (pintype "bidirectional"))
      (node (ref "PI1") (pin "111") (pinfunction "11_111") (pintype "passive"))
    )
    (net (code "119") (name "PCIE_CLK_P") (class "Default")
      (node (ref "PCIE") (pin "55") (pinfunction "REFCLK_P_55") (pintype "bidirectional"))
      (node (ref "PI1") (pin "109") (pinfunction "9_109") (pintype "passive"))
    )
    (net (code "120") (name "PCIE_NCLKREQ") (class "Default")
      (node (ref "PCIE") (pin "52") (pinfunction "~{CLKREQ}_52") (pintype "bidirectional"))
      (node (ref "PI1") (pin "101") (pinfunction "1_101") (pintype "passive"))
    )
    (net (code "121") (name "PCIE_NRST") (class "Default")
      (node (ref "PCIE") (pin "50") (pinfunction "~{PERST}_50") (pintype "bidirectional"))
      (node (ref "PI1") (pin "110") (pinfunction "10_110") (pintype "passive"))
    )
    (net (code "122") (name "PCIE_NWAKE") (class "Default")
      (node (ref "PCIE") (pin "54") (pinfunction "~{PEWAKE}_54") (pintype "bidirectional"))
      (node (ref "PI1") (pin "103") (pinfunction "3_103") (pintype "passive"))
    )
    (net (code "123") (name "PCIE_PWR_EN") (class "Default")
      (node (ref "IC5") (pin "7") (pinfunction "EN_7") (pintype "bidirectional"))
      (node (ref "PI1") (pin "105") (pinfunction "5_105") (pintype "passive"))
      (node (ref "R11") (pin "1") (pinfunction "1_1") (pintype "passive"))
    )
    (net (code "124") (name "PCIE_RX_N") (class "Default")
      (node (ref "PCIE") (pin "43") (pinfunction "PET_P0_43") (pintype "bidirectional"))
      (node (ref "PI1") (pin "117") (pinfunction "17_117") (pintype "passive"))
    )
    (net (code "125") (name "PCIE_RX_P") (class "Default")
      (node (ref "PCIE") (pin "41") (pinfunction "PET_N0_41") (pintype "bidirectional"))
      (node (ref "PI1") (pin "115") (pinfunction "15_115") (pintype "passive"))
    )
    (net (code "126") (name "PCIE_TX_N") (class "Default")
      (node (ref "PCIE") (pin "49") (pinfunction "PER_P0_49") (pintype "bidirectional"))
      (node (ref "PI1") (pin "123") (pinfunction "23_123") (pintype "passive"))
    )
    (net (code "127") (name "PCIE_TX_P") (class "Default")
      (node (ref "PCIE") (pin "47") (pinfunction "PER_N0_47") (pintype "bidirectional"))
      (node (ref "PI1") (pin "121") (pinfunction "21_121") (pintype "passive"))
    )
    (net (code "128") (name "PMIC_ENABLE") (class "Default")
      (node (ref "JP2") (pin "12") (pinfunction "12_12") (pintype "bidirectional"))
      (node (ref "PI1") (pin "100") (pinfunction "100_100") (pintype "passive"))
    )
    (net (code "129") (name "PWM") (class "Default")
      (node (ref "FAN") (pin "3") (pinfunction "P$3_3") (pintype "bidirectional"))
      (node (ref "PI1") (pin "20") (pinfunction "20_20") (pintype "passive"))
    )
    (net (code "130") (name "PWR_BUT") (class "Default")
      (node (ref "JP2") (pin "14") (pinfunction "14_14") (pintype "bidirectional"))
      (node (ref "PI1") (pin "91") (pinfunction "91_91") (pintype "passive"))
      (node (ref "SW1") (pin "2") (pinfunction "2_2") (pintype "passive"))
      (node (ref "TP-BTN") (pin "TP") (pinfunction "P$1_TP") (pintype "bidirectional"))
    )
    (net (code "131") (name "RP2040_RST0") (class "Default")
      (node (ref "CON3") (pin "23") (pinfunction "23_23") (pintype "bidirectional"))
      (node (ref "MODULE_AIO") (pin "B18") (pinfunction "18_B18") (pintype "passive"))
    )
    (net (code "132") (name "RP2040_RST1") (class "Default")
      (node (ref "CON3") (pin "21") (pinfunction "21_21") (pintype "bidirectional"))
      (node (ref "MODULE_DIO") (pin "B18") (pinfunction "18_B18") (pintype "passive"))
    )
    (net (code "133") (name "SCL0") (class "Default")
      (node (ref "J3") (pin "20") (pinfunction "20_20") (pintype "passive"))
      (node (ref "PI1") (pin "79") (pinfunction "79_79") (pintype "passive"))
    )
    (net (code "134") (name "SCL1") (class "Default")
      (node (ref "ID") (pin "2") (pinfunction "2_2") (pintype "bidirectional"))
      (node (ref "J4") (pin "20") (pinfunction "20_20") (pintype "passive"))
      (node (ref "R4") (pin "2") (pinfunction "2_2") (pintype "passive"))
    )
    (net (code "135") (name "SDA0") (class "Default")
      (node (ref "J3") (pin "21") (pinfunction "21_21") (pintype "passive"))
      (node (ref "PI1") (pin "81") (pinfunction "81_81") (pintype "passive"))
    )
    (net (code "136") (name "SDA1") (class "Default")
      (node (ref "ID") (pin "4") (pinfunction "4_4") (pintype "bidirectional"))
      (node (ref "J4") (pin "21") (pinfunction "21_21") (pintype "passive"))
      (node (ref "R3") (pin "2") (pinfunction "2_2") (pintype "passive"))
    )
    (net (code "137") (name "SDO_A_0") (class "Default")
      (node (ref "CON2") (pin "15") (pinfunction "15_15") (pintype "bidirectional"))
      (node (ref "MODULE_AIO") (pin "A17") (pinfunction "17_A17") (pintype "passive"))
    )
    (net (code "138") (name "SDO_A_1") (class "Default")
      (node (ref "CON2") (pin "13") (pinfunction "13_13") (pintype "bidirectional"))
      (node (ref "MODULE_AIO") (pin "A18") (pinfunction "18_A18") (pintype "passive"))
    )
    (net (code "139") (name "SDO_A_2") (class "Default")
      (node (ref "CON2") (pin "11") (pinfunction "11_11") (pintype "bidirectional"))
      (node (ref "MODULE_AIO") (pin "A19") (pinfunction "19_A19") (pintype "passive"))
    )
    (net (code "140") (name "SDO_A_3") (class "Default")
      (node (ref "CON2") (pin "9") (pinfunction "9_9") (pintype "bidirectional"))
      (node (ref "MODULE_AIO") (pin "A20") (pinfunction "20_A20") (pintype "passive"))
    )
    (net (code "141") (name "SDO_B_0") (class "Default")
      (node (ref "CON2") (pin "7") (pinfunction "7_7") (pintype "bidirectional"))
      (node (ref "MODULE_AIO") (pin "A21") (pinfunction "21_A21") (pintype "passive"))
    )
    (net (code "142") (name "SDO_B_1") (class "Default")
      (node (ref "CON2") (pin "5") (pinfunction "5_5") (pintype "bidirectional"))
      (node (ref "MODULE_AIO") (pin "A22") (pinfunction "22_A22") (pintype "passive"))
    )
    (net (code "143") (name "SDO_B_2") (class "Default")
      (node (ref "CON2") (pin "3") (pinfunction "3_3") (pintype "bidirectional"))
      (node (ref "MODULE_AIO") (pin "A23") (pinfunction "23_A23") (pintype "passive"))
    )
    (net (code "144") (name "SDO_B_3") (class "Default")
      (node (ref "CON2") (pin "1") (pinfunction "1_1") (pintype "bidirectional"))
      (node (ref "MODULE_AIO") (pin "A24") (pinfunction "24_A24") (pintype "passive"))
    )
    (net (code "145") (name "SD_CLK") (class "Default")
      (node (ref "PI1") (pin "58") (pinfunction "58_58") (pintype "passive"))
      (node (ref "SD1") (pin "CLK") (pinfunction "CLK_CLK") (pintype "bidirectional"))
    )
    (net (code "146") (name "SD_CMD") (class "Default")
      (node (ref "PI1") (pin "61") (pinfunction "61_61") (pintype "passive"))
      (node (ref "SD1") (pin "CMD") (pinfunction "CMD_CMD") (pintype "bidirectional"))
    )
    (net (code "147") (name "SD_DAT0") (class "Default")
      (node (ref "PI1") (pin "64") (pinfunction "64_64") (pintype "passive"))
      (node (ref "SD1") (pin "DAT0") (pinfunction "DAT0_DAT0") (pintype "bidirectional"))
    )
    (net (code "148") (name "SD_DAT1") (class "Default")
      (node (ref "PI1") (pin "68") (pinfunction "68_68") (pintype "passive"))
      (node (ref "SD1") (pin "DAT1") (pinfunction "DAT1_DAT1") (pintype "bidirectional"))
    )
    (net (code "149") (name "SD_DAT2") (class "Default")
      (node (ref "PI1") (pin "70") (pinfunction "70_70") (pintype "passive"))
      (node (ref "SD1") (pin "DAT2") (pinfunction "DAT2_DAT2") (pintype "bidirectional"))
    )
    (net (code "150") (name "SD_DAT3") (class "Default")
      (node (ref "PI1") (pin "62") (pinfunction "62_62") (pintype "passive"))
      (node (ref "SD1") (pin "DAT3/CD") (pinfunction "CD/DAT3_DAT3/CD") (pintype "bidirectional"))
    )
    (net (code "151") (name "SD_PWR") (class "Default")
      (node (ref "C10") (pin "1") (pinfunction "1_1") (pintype "passive"))
      (node (ref "IC1") (pin "1") (pinfunction "OUT_1") (pintype "power_in"))
      (node (ref "SD1") (pin "VDD") (pinfunction "VDD_VDD") (pintype "bidirectional"))
      (node (ref "TP-VSD") (pin "TP") (pinfunction "P$1_TP") (pintype "bidirectional"))
    )
    (net (code "152") (name "SD_PWR_ON") (class "Default")
      (node (ref "IC1") (pin "4") (pinfunction "EN_4") (pintype "bidirectional"))
      (node (ref "PI1") (pin "76") (pinfunction "76_76") (pintype "passive"))
    )
    (net (code "153") (name "SPI_ADC_CS") (class "Default")
      (node (ref "CON2") (pin "39") (pinfunction "39_39") (pintype "bidirectional"))
      (node (ref "MODULE_AIO") (pin "A2") (pinfunction "2_A2") (pintype "passive"))
    )
    (net (code "154") (name "SPI_AIOMODULE_CS0") (class "Default")
      (node (ref "CON3") (pin "5") (pinfunction "5_5") (pintype "bidirectional"))
      (node (ref "MODULE_AIO") (pin "A29") (pinfunction "29_A29") (pintype "passive"))
      (node (ref "MODULE_AIO") (pin "B29") (pinfunction "29_B29") (pintype "passive"))
    )
    (net (code "155") (name "SPI_AIOMODULE_MISO") (class "Default")
      (node (ref "CON3") (pin "11") (pinfunction "11_11") (pintype "bidirectional"))
      (node (ref "MODULE_AIO") (pin "A26") (pinfunction "26_A26") (pintype "passive"))
      (node (ref "MODULE_AIO") (pin "B26") (pinfunction "26_B26") (pintype "passive"))
    )
    (net (code "156") (name "SPI_AIOMODULE_MOSI") (class "Default")
      (node (ref "CON3") (pin "9") (pinfunction "9_9") (pintype "bidirectional"))
      (node (ref "MODULE_AIO") (pin "A27") (pinfunction "27_A27") (pintype "passive"))
      (node (ref "MODULE_AIO") (pin "B27") (pinfunction "27_B27") (pintype "passive"))
    )
    (net (code "157") (name "SPI_AIOMODULE_SCK") (class "Default")
      (node (ref "CON3") (pin "7") (pinfunction "7_7") (pintype "bidirectional"))
      (node (ref "MODULE_AIO") (pin "A28") (pinfunction "28_A28") (pintype "passive"))
      (node (ref "MODULE_AIO") (pin "B28") (pinfunction "28_B28") (pintype "passive"))
    )
    (net (code "158") (name "SPI_DAC_CS") (class "Default")
      (node (ref "CON2") (pin "21") (pinfunction "21_21") (pintype "bidirectional"))
      (node (ref "MODULE_AIO") (pin "B2") (pinfunction "2_B2") (pintype "passive"))
    )
    (net (code "159") (name "SPI_DIOMODULE_CS1") (class "Default")
      (node (ref "CON3") (pin "3") (pinfunction "3_3") (pintype "bidirectional"))
      (node (ref "MODULE_DIO") (pin "A29") (pinfunction "29_A29") (pintype "passive"))
      (node (ref "MODULE_DIO") (pin "B29") (pinfunction "29_B29") (pintype "passive"))
    )
    (net (code "160") (name "SPI_DIOMODULE_MISO") (class "Default")
      (node (ref "MODULE_DIO") (pin "A26") (pinfunction "26_A26") (pintype "passive"))
      (node (ref "MODULE_DIO") (pin "B26") (pinfunction "26_B26") (pintype "passive"))
    )
    (net (code "161") (name "SPI_DIOMODULE_MOSI") (class "Default")
      (node (ref "MODULE_DIO") (pin "A27") (pinfunction "27_A27") (pintype "passive"))
      (node (ref "MODULE_DIO") (pin "B27") (pinfunction "27_B27") (pintype "passive"))
    )
    (net (code "162") (name "SPI_DIOMODULE_SCK") (class "Default")
      (node (ref "MODULE_DIO") (pin "A28") (pinfunction "28_A28") (pintype "passive"))
      (node (ref "MODULE_DIO") (pin "B28") (pinfunction "28_B28") (pintype "passive"))
    )
    (net (code "163") (name "SPI_DIO_CS0") (class "Default")
      (node (ref "CON3") (pin "33") (pinfunction "33_33") (pintype "bidirectional"))
      (node (ref "MODULE_DIO") (pin "A2") (pinfunction "2_A2") (pintype "passive"))
    )
    (net (code "164") (name "SPI_DIO_CS1") (class "Default")
      (node (ref "CON3") (pin "31") (pinfunction "31_31") (pintype "bidirectional"))
      (node (ref "MODULE_DIO") (pin "A3") (pinfunction "3_A3") (pintype "passive"))
    )
    (net (code "165") (name "SPI_MISO") (class "Default")
      (node (ref "CON2") (pin "29") (pinfunction "29_29") (pintype "bidirectional"))
      (node (ref "MODULE_AIO") (pin "A7") (pinfunction "7_A7") (pintype "passive"))
      (node (ref "MODULE_AIO") (pin "B7") (pinfunction "7_B7") (pintype "passive"))
      (node (ref "MODULE_DIO") (pin "A7") (pinfunction "7_A7") (pintype "passive"))
      (node (ref "MODULE_DIO") (pin "B7") (pinfunction "7_B7") (pintype "passive"))
    )
    (net (code "166") (name "SPI_MOSI") (class "Default")
      (node (ref "CON2") (pin "31") (pinfunction "31_31") (pintype "bidirectional"))
      (node (ref "MODULE_AIO") (pin "A6") (pinfunction "6_A6") (pintype "passive"))
      (node (ref "MODULE_AIO") (pin "B6") (pinfunction "6_B6") (pintype "passive"))
      (node (ref "MODULE_DIO") (pin "A6") (pinfunction "6_A6") (pintype "passive"))
      (node (ref "MODULE_DIO") (pin "B6") (pinfunction "6_B6") (pintype "passive"))
    )
    (net (code "167") (name "SPI_PGA_CS0") (class "Default")
      (node (ref "CON2") (pin "37") (pinfunction "37_37") (pintype "bidirectional"))
      (node (ref "MODULE_AIO") (pin "A3") (pinfunction "3_A3") (pintype "passive"))
    )
    (net (code "168") (name "SPI_PGA_CS1") (class "Default")
      (node (ref "CON2") (pin "35") (pinfunction "35_35") (pintype "bidirectional"))
      (node (ref "MODULE_AIO") (pin "A4") (pinfunction "4_A4") (pintype "passive"))
    )
    (net (code "169") (name "SPI_SCK") (class "Default")
      (node (ref "CON2") (pin "33") (pinfunction "33_33") (pintype "bidirectional"))
      (node (ref "MODULE_AIO") (pin "A5") (pinfunction "5_A5") (pintype "passive"))
      (node (ref "MODULE_AIO") (pin "B5") (pinfunction "5_B5") (pintype "passive"))
      (node (ref "MODULE_DIO") (pin "A5") (pinfunction "5_A5") (pintype "passive"))
      (node (ref "MODULE_DIO") (pin "B5") (pinfunction "5_B5") (pintype "passive"))
    )
    (net (code "170") (name "SWCLK") (class "Default")
      (node (ref "CON3") (pin "15") (pinfunction "15_15") (pintype "bidirectional"))
      (node (ref "MODULE_AIO") (pin "B23") (pinfunction "23_B23") (pintype "passive"))
      (node (ref "MODULE_DIO") (pin "B23") (pinfunction "23_B23") (pintype "passive"))
    )
    (net (code "171") (name "SWDIO") (class "Default")
      (node (ref "CON3") (pin "13") (pinfunction "13_13") (pintype "bidirectional"))
      (node (ref "MODULE_AIO") (pin "B24") (pinfunction "24_B24") (pintype "passive"))
      (node (ref "MODULE_DIO") (pin "B24") (pinfunction "24_B24") (pintype "passive"))
    )
    (net (code "172") (name "SYNC_OUT") (class "Default")
      (node (ref "JP2") (pin "6") (pinfunction "6_6") (pintype "bidirectional"))
      (node (ref "PI1") (pin "17") (pinfunction "17_17") (pintype "passive"))
    )
    (net (code "173") (name "TACHO") (class "Default")
      (node (ref "FAN") (pin "1") (pinfunction "P$1_1") (pintype "bidirectional"))
      (node (ref "PI1") (pin "15") (pinfunction "15_15") (pintype "passive"))
    )
    (net (code "174") (name "TR0_TAP") (class "Default")
      (node (ref "ETH1") (pin "VC1") (pinfunction "VC1_VC1") (pintype "bidirectional"))
      (node (ref "POE") (pin "3") (pinfunction "3_3") (pintype "bidirectional"))
    )
    (net (code "175") (name "TR1_TAP") (class "Default")
      (node (ref "ETH1") (pin "VC2") (pinfunction "VC2_VC2") (pintype "bidirectional"))
      (node (ref "POE") (pin "1") (pinfunction "1_1") (pintype "bidirectional"))
    )
    (net (code "176") (name "TR2_TAP") (class "Default")
      (node (ref "ETH1") (pin "VC3") (pinfunction "VC3_VC3") (pintype "bidirectional"))
      (node (ref "POE") (pin "2") (pinfunction "2_2") (pintype "bidirectional"))
    )
    (net (code "177") (name "TR3_TAP") (class "Default")
      (node (ref "ETH1") (pin "VC4") (pinfunction "VC4_VC4") (pintype "bidirectional"))
      (node (ref "POE") (pin "4") (pinfunction "4_4") (pintype "bidirectional"))
    )
    (net (code "178") (name "UART0_RX") (class "Default")
      (node (ref "CON3") (pin "19") (pinfunction "19_19") (pintype "bidirectional"))
      (node (ref "MODULE_AIO") (pin "B20") (pinfunction "20_B20") (pintype "passive"))
      (node (ref "MODULE_DIO") (pin "B20") (pinfunction "20_B20") (pintype "passive"))
    )
    (net (code "179") (name "UART0_TX") (class "Default")
      (node (ref "CON3") (pin "17") (pinfunction "17_17") (pintype "bidirectional"))
      (node (ref "MODULE_AIO") (pin "B21") (pinfunction "21_B21") (pintype "passive"))
      (node (ref "MODULE_DIO") (pin "B21") (pinfunction "21_B21") (pintype "passive"))
    )
    (net (code "180") (name "USB3A_DP_N") (class "Default")
      (node (ref "J1") (pin "2") (pinfunction "D-_2") (pintype "passive"))
      (node (ref "PI1") (pin "135") (pinfunction "35_135") (pintype "passive"))
    )
    (net (code "181") (name "USB3A_DP_P") (class "Default")
      (node (ref "J1") (pin "3") (pinfunction "D+_3") (pintype "passive"))
      (node (ref "PI1") (pin "133") (pinfunction "33_133") (pintype "passive"))
    )
    (net (code "182") (name "USB3A_SSRX_N") (class "Default")
      (node (ref "J1") (pin "5") (pinfunction "STDA_SSRX-_5") (pintype "passive"))
      (node (ref "PI1") (pin "127") (pinfunction "27_127") (pintype "passive"))
    )
    (net (code "183") (name "USB3A_SSRX_P") (class "Default")
      (node (ref "J1") (pin "6") (pinfunction "STDA_SSRX+_6") (pintype "passive"))
      (node (ref "PI1") (pin "129") (pinfunction "29_129") (pintype "passive"))
    )
    (net (code "184") (name "USB3A_SSTX_N") (class "Default")
      (node (ref "J1") (pin "8") (pinfunction "STDA_SSTX-_8") (pintype "passive"))
      (node (ref "PI1") (pin "139") (pinfunction "39_139") (pintype "passive"))
    )
    (net (code "185") (name "USB3A_SSTX_P") (class "Default")
      (node (ref "J1") (pin "9") (pinfunction "STDA_SSTX+_9") (pintype "passive"))
      (node (ref "PI1") (pin "141") (pinfunction "41_141") (pintype "passive"))
    )
    (net (code "186") (name "USB3B_DP_N") (class "Default")
      (node (ref "J2") (pin "2") (pinfunction "D-_2") (pintype "passive"))
      (node (ref "PI1") (pin "166") (pinfunction "66_166") (pintype "passive"))
    )
    (net (code "187") (name "USB3B_DP_P") (class "Default")
      (node (ref "J2") (pin "3") (pinfunction "D+_3") (pintype "passive"))
      (node (ref "PI1") (pin "164") (pinfunction "64_164") (pintype "passive"))
    )
    (net (code "188") (name "USB3B_SSRX_N") (class "Default")
      (node (ref "J2") (pin "5") (pinfunction "STDA_SSRX-_5") (pintype "passive"))
      (node (ref "PI1") (pin "158") (pinfunction "58_158") (pintype "passive"))
    )
    (net (code "189") (name "USB3B_SSRX_P") (class "Default")
      (node (ref "J2") (pin "6") (pinfunction "STDA_SSRX+_6") (pintype "passive"))
      (node (ref "PI1") (pin "160") (pinfunction "60_160") (pintype "passive"))
    )
    (net (code "190") (name "USB3B_SSTX_N") (class "Default")
      (node (ref "J2") (pin "8") (pinfunction "STDA_SSTX-_8") (pintype "passive"))
      (node (ref "PI1") (pin "170") (pinfunction "70_170") (pintype "passive"))
    )
    (net (code "191") (name "USB3B_SSTX_P") (class "Default")
      (node (ref "J2") (pin "9") (pinfunction "STDA_SSTX+_9") (pintype "passive"))
      (node (ref "PI1") (pin "172") (pinfunction "72_172") (pintype "passive"))
    )
    (net (code "192") (name "USBOTG_ID") (class "Default")
      (node (ref "JP2") (pin "10") (pinfunction "10_10") (pintype "bidirectional"))
      (node (ref "PI1") (pin "102") (pinfunction "2_102") (pintype "passive"))
    )
    (net (code "193") (name "USB_DP_N") (class "Default")
      (node (ref "PI1") (pin "104") (pinfunction "4_104") (pintype "passive"))
      (node (ref "USBC") (pin "A7") (pinfunction "D-1_A7") (pintype "passive"))
      (node (ref "USBC") (pin "B7") (pinfunction "D-2_B7") (pintype "passive"))
    )
    (net (code "194") (name "USB_DP_P") (class "Default")
      (node (ref "PI1") (pin "106") (pinfunction "6_106") (pintype "passive"))
      (node (ref "USBC") (pin "A6") (pinfunction "D+1_A6") (pintype "passive"))
      (node (ref "USBC") (pin "B6") (pinfunction "D+2_B6") (pintype "passive"))
    )
    (net (code "195") (name "VBAT") (class "Default")
      (node (ref "PI1") (pin "75") (pinfunction "75_75") (pintype "passive"))
    )
    (net (code "196") (name "VBUS") (class "Default")
      (node (ref "C6") (pin "1") (pinfunction "1_1") (pintype "passive"))
      (node (ref "C7") (pin "1") (pinfunction "1_1") (pintype "passive"))
      (node (ref "C8") (pin "1") (pinfunction "1_1") (pintype "passive"))
      (node (ref "IC2") (pin "6") (pinfunction "OUT_6") (pintype "bidirectional"))
      (node (ref "J1") (pin "1") (pinfunction "VBUS_1") (pintype "passive"))
      (node (ref "J2") (pin "1") (pinfunction "VBUS_1") (pintype "passive"))
      (node (ref "TP-VBUS") (pin "TP") (pinfunction "P$1_TP") (pintype "bidirectional"))
    )
    (net (code "197") (name "VBUS_EN") (class "Default")
      (node (ref "IC2") (pin "3") (pinfunction "EN_3") (pintype "bidirectional"))
      (node (ref "PI1") (pin "112") (pinfunction "12_112") (pintype "passive"))
    )
    (net (code "198") (name "WL_NDIS") (class "Default")
      (node (ref "JP3") (pin "1") (pinfunction "1_1") (pintype "bidirectional"))
      (node (ref "PI1") (pin "90") (pinfunction "90_90") (pintype "passive"))
    )
    (net (code "199") (name "unconnected-(CON2-Pad2)") (class "Default")
      (node (ref "CON2") (pin "2") (pinfunction "2_2") (pintype "bidirectional"))
    )
    (net (code "200") (name "unconnected-(CON2-Pad4)") (class "Default")
      (node (ref "CON2") (pin "4") (pinfunction "4_4") (pintype "bidirectional"))
    )
    (net (code "201") (name "unconnected-(CON2-Pad6)") (class "Default")
      (node (ref "CON2") (pin "6") (pinfunction "6_6") (pintype "bidirectional"))
    )
    (net (code "202") (name "unconnected-(CON2-Pad8)") (class "Default")
      (node (ref "CON2") (pin "8") (pinfunction "8_8") (pintype "bidirectional"))
    )
    (net (code "203") (name "unconnected-(CON2-Pad10)") (class "Default")
      (node (ref "CON2") (pin "10") (pinfunction "10_10") (pintype "bidirectional"))
    )
    (net (code "204") (name "unconnected-(CON2-Pad12)") (class "Default")
      (node (ref "CON2") (pin "12") (pinfunction "12_12") (pintype "bidirectional"))
    )
    (net (code "205") (name "unconnected-(CON2-Pad14)") (class "Default")
      (node (ref "CON2") (pin "14") (pinfunction "14_14") (pintype "bidirectional"))
    )
    (net (code "206") (name "unconnected-(CON2-Pad16)") (class "Default")
      (node (ref "CON2") (pin "16") (pinfunction "16_16") (pintype "bidirectional"))
    )
    (net (code "207") (name "unconnected-(CON3-Pad26)") (class "Default")
      (node (ref "CON3") (pin "26") (pinfunction "26_26") (pintype "bidirectional"))
    )
    (net (code "208") (name "unconnected-(CON3-Pad28)") (class "Default")
      (node (ref "CON3") (pin "28") (pinfunction "28_28") (pintype "bidirectional"))
    )
    (net (code "209") (name "unconnected-(CON3-Pad35)") (class "Default")
      (node (ref "CON3") (pin "35") (pinfunction "35_35") (pintype "bidirectional"))
    )
    (net (code "210") (name "unconnected-(CON3-Pad36)") (class "Default")
      (node (ref "CON3") (pin "36") (pinfunction "36_36") (pintype "bidirectional"))
    )
    (net (code "211") (name "unconnected-(CON3-Pad37)") (class "Default")
      (node (ref "CON3") (pin "37") (pinfunction "37_37") (pintype "bidirectional"))
    )
    (net (code "212") (name "unconnected-(CON3-Pad38)") (class "Default")
      (node (ref "CON3") (pin "38") (pinfunction "38_38") (pintype "bidirectional"))
    )
    (net (code "213") (name "unconnected-(CON3-Pad39)") (class "Default")
      (node (ref "CON3") (pin "39") (pinfunction "39_39") (pintype "bidirectional"))
    )
    (net (code "214") (name "unconnected-(CON3-Pad40)") (class "Default")
      (node (ref "CON3") (pin "40") (pinfunction "40_40") (pintype "bidirectional"))
    )
    (net (code "215") (name "unconnected-(HDMI1-CEC-Pad14)") (class "Default")
      (node (ref "HDMI1") (pin "14") (pinfunction "CEC_14") (pintype "passive"))
    )
    (net (code "216") (name "unconnected-(HDMI2-CEC-Pad14)") (class "Default")
      (node (ref "HDMI2") (pin "14") (pinfunction "CEC_14") (pintype "passive"))
    )
    (net (code "217") (name "unconnected-(IC1-NFLG-Pad3)") (class "Default")
      (node (ref "IC1") (pin "3") (pinfunction "NFLG_3") (pintype "bidirectional"))
    )
    (net (code "218") (name "unconnected-(IC2-~{FAULT}-Pad4)") (class "Default")
      (node (ref "IC2") (pin "4") (pinfunction "~{FAULT}_4") (pintype "bidirectional"))
    )
    (net (code "219") (name "unconnected-(IC5-NC-Pad5)") (class "Default")
      (node (ref "IC5") (pin "5") (pinfunction "NC_5") (pintype "no_connect"))
    )
    (net (code "220") (name "unconnected-(IC5-PG-Pad2)") (class "Default")
      (node (ref "IC5") (pin "2") (pinfunction "PG_2") (pintype "bidirectional"))
    )
    (net (code "221") (name "unconnected-(J4-Pad18)") (class "Default")
      (node (ref "J4") (pin "18") (pinfunction "18_18") (pintype "passive"))
    )
    (net (code "222") (name "unconnected-(JP2-Pad8)") (class "Default")
      (node (ref "JP2") (pin "8") (pinfunction "8_8") (pintype "bidirectional"))
    )
    (net (code "223") (name "unconnected-(MODULE_AIOB-3-PadB3)") (class "Default")
      (node (ref "MODULE_AIO") (pin "B3") (pinfunction "3_B3") (pintype "passive"))
    )
    (net (code "224") (name "unconnected-(MODULE_AIOB-4-PadB4)") (class "Default")
      (node (ref "MODULE_AIO") (pin "B4") (pinfunction "4_B4") (pintype "passive"))
    )
    (net (code "225") (name "unconnected-(MODULE_AIOB-11-PadB11)") (class "Default")
      (node (ref "MODULE_AIO") (pin "B11") (pinfunction "11_B11") (pintype "passive"))
    )
    (net (code "226") (name "unconnected-(MODULE_AIOB-17-PadB17)") (class "Default")
      (node (ref "MODULE_AIO") (pin "B17") (pinfunction "17_B17") (pintype "passive"))
    )
    (net (code "227") (name "unconnected-(MODULE_DIOA-4-PadA4)") (class "Default")
      (node (ref "MODULE_DIO") (pin "A4") (pinfunction "4_A4") (pintype "passive"))
    )
    (net (code "228") (name "unconnected-(MODULE_DIOA-17-PadA17)") (class "Default")
      (node (ref "MODULE_DIO") (pin "A17") (pinfunction "17_A17") (pintype "passive"))
    )
    (net (code "229") (name "unconnected-(MODULE_DIOA-18-PadA18)") (class "Default")
      (node (ref "MODULE_DIO") (pin "A18") (pinfunction "18_A18") (pintype "passive"))
    )
    (net (code "230") (name "unconnected-(MODULE_DIOA-19-PadA19)") (class "Default")
      (node (ref "MODULE_DIO") (pin "A19") (pinfunction "19_A19") (pintype "passive"))
    )
    (net (code "231") (name "unconnected-(MODULE_DIOA-20-PadA20)") (class "Default")
      (node (ref "MODULE_DIO") (pin "A20") (pinfunction "20_A20") (pintype "passive"))
    )
    (net (code "232") (name "unconnected-(MODULE_DIOA-21-PadA21)") (class "Default")
      (node (ref "MODULE_DIO") (pin "A21") (pinfunction "21_A21") (pintype "passive"))
    )
    (net (code "233") (name "unconnected-(MODULE_DIOA-22-PadA22)") (class "Default")
      (node (ref "MODULE_DIO") (pin "A22") (pinfunction "22_A22") (pintype "passive"))
    )
    (net (code "234") (name "unconnected-(MODULE_DIOA-23-PadA23)") (class "Default")
      (node (ref "MODULE_DIO") (pin "A23") (pinfunction "23_A23") (pintype "passive"))
    )
    (net (code "235") (name "unconnected-(MODULE_DIOA-24-PadA24)") (class "Default")
      (node (ref "MODULE_DIO") (pin "A24") (pinfunction "24_A24") (pintype "passive"))
    )
    (net (code "236") (name "unconnected-(MODULE_DIOB-2-PadB2)") (class "Default")
      (node (ref "MODULE_DIO") (pin "B2") (pinfunction "2_B2") (pintype "passive"))
    )
    (net (code "237") (name "unconnected-(MODULE_DIOB-3-PadB3)") (class "Default")
      (node (ref "MODULE_DIO") (pin "B3") (pinfunction "3_B3") (pintype "passive"))
    )
    (net (code "238") (name "unconnected-(MODULE_DIOB-4-PadB4)") (class "Default")
      (node (ref "MODULE_DIO") (pin "B4") (pinfunction "4_B4") (pintype "passive"))
    )
    (net (code "239") (name "unconnected-(MODULE_DIOB-11-PadB11)") (class "Default")
      (node (ref "MODULE_DIO") (pin "B11") (pinfunction "11_B11") (pintype "passive"))
    )
    (net (code "240") (name "unconnected-(MODULE_DIOB-12-PadB12)") (class "Default")
      (node (ref "MODULE_DIO") (pin "B12") (pinfunction "12_B12") (pintype "passive"))
    )
    (net (code "241") (name "unconnected-(MODULE_DIOB-13-PadB13)") (class "Default")
      (node (ref "MODULE_DIO") (pin "B13") (pinfunction "13_B13") (pintype "passive"))
    )
    (net (code "242") (name "unconnected-(MODULE_DIOB-17-PadB17)") (class "Default")
      (node (ref "MODULE_DIO") (pin "B17") (pinfunction "17_B17") (pintype "passive"))
    )
    (net (code "243") (name "unconnected-(PCIE-DEVSLP-Pad38)") (class "Default")
      (node (ref "PCIE") (pin "38") (pinfunction "DEVSLP_38") (pintype "bidirectional"))
    )
    (net (code "244") (name "unconnected-(PCIE-NC1-Pad58)") (class "Default")
      (node (ref "PCIE") (pin "58") (pinfunction "NC1_58") (pintype "bidirectional"))
    )
    (net (code "245") (name "unconnected-(PCIE-NC2-Pad56)") (class "Default")
      (node (ref "PCIE") (pin "56") (pinfunction "NC2_56") (pintype "bidirectional"))
    )
    (net (code "246") (name "unconnected-(PCIE-NC3-Pad48)") (class "Default")
      (node (ref "PCIE") (pin "48") (pinfunction "NC3_48") (pintype "bidirectional"))
    )
    (net (code "247") (name "unconnected-(PCIE-NC4-Pad46)") (class "Default")
      (node (ref "PCIE") (pin "46") (pinfunction "NC4_46") (pintype "bidirectional"))
    )
    (net (code "248") (name "unconnected-(PCIE-NC5-Pad44)") (class "Default")
      (node (ref "PCIE") (pin "44") (pinfunction "NC5_44") (pintype "bidirectional"))
    )
    (net (code "249") (name "unconnected-(PCIE-NC6-Pad42)") (class "Default")
      (node (ref "PCIE") (pin "42") (pinfunction "NC6_42") (pintype "bidirectional"))
    )
    (net (code "250") (name "unconnected-(PCIE-NC7-Pad40)") (class "Default")
      (node (ref "PCIE") (pin "40") (pinfunction "NC7_40") (pintype "bidirectional"))
    )
    (net (code "251") (name "unconnected-(PCIE-NC8-Pad36)") (class "Default")
      (node (ref "PCIE") (pin "36") (pinfunction "NC8_36") (pintype "bidirectional"))
    )
    (net (code "252") (name "unconnected-(PCIE-NC9-Pad34)") (class "Default")
      (node (ref "PCIE") (pin "34") (pinfunction "NC9_34") (pintype "bidirectional"))
    )
    (net (code "253") (name "unconnected-(PCIE-NC10-Pad32)") (class "Default")
      (node (ref "PCIE") (pin "32") (pinfunction "NC10_32") (pintype "bidirectional"))
    )
    (net (code "254") (name "unconnected-(PCIE-NC11-Pad30)") (class "Default")
      (node (ref "PCIE") (pin "30") (pinfunction "NC11_30") (pintype "bidirectional"))
    )
    (net (code "255") (name "unconnected-(PCIE-NC12-Pad28)") (class "Default")
      (node (ref "PCIE") (pin "28") (pinfunction "NC12_28") (pintype "bidirectional"))
    )
    (net (code "256") (name "unconnected-(PCIE-NC13-Pad26)") (class "Default")
      (node (ref "PCIE") (pin "26") (pinfunction "NC13_26") (pintype "bidirectional"))
    )
    (net (code "257") (name "unconnected-(PCIE-NC14-Pad24)") (class "Default")
      (node (ref "PCIE") (pin "24") (pinfunction "NC14_24") (pintype "bidirectional"))
    )
    (net (code "258") (name "unconnected-(PCIE-NC15-Pad22)") (class "Default")
      (node (ref "PCIE") (pin "22") (pinfunction "NC15_22") (pintype "bidirectional"))
    )
    (net (code "259") (name "unconnected-(PCIE-NC16-Pad20)") (class "Default")
      (node (ref "PCIE") (pin "20") (pinfunction "NC16_20") (pintype "bidirectional"))
    )
    (net (code "260") (name "unconnected-(PCIE-NC17-Pad8)") (class "Default")
      (node (ref "PCIE") (pin "8") (pinfunction "NC17_8") (pintype "bidirectional"))
    )
    (net (code "261") (name "unconnected-(PCIE-NC18-Pad6)") (class "Default")
      (node (ref "PCIE") (pin "6") (pinfunction "NC18_6") (pintype "bidirectional"))
    )
    (net (code "262") (name "unconnected-(PCIE-NC19-Pad67)") (class "Default")
      (node (ref "PCIE") (pin "67") (pinfunction "NC19_67") (pintype "bidirectional"))
    )
    (net (code "263") (name "unconnected-(PCIE-PEDET-Pad69)") (class "Default")
      (node (ref "PCIE") (pin "69") (pinfunction "PEDET_69") (pintype "bidirectional"))
    )
    (net (code "264") (name "unconnected-(PCIE-PER_N1-Pad35)") (class "Default")
      (node (ref "PCIE") (pin "35") (pinfunction "PER_N1_35") (pintype "bidirectional"))
    )
    (net (code "265") (name "unconnected-(PCIE-PER_N2-Pad23)") (class "Default")
      (node (ref "PCIE") (pin "23") (pinfunction "PER_N2_23") (pintype "bidirectional"))
    )
    (net (code "266") (name "unconnected-(PCIE-PER_N3-Pad11)") (class "Default")
      (node (ref "PCIE") (pin "11") (pinfunction "PER_N3_11") (pintype "bidirectional"))
    )
    (net (code "267") (name "unconnected-(PCIE-PER_P1-Pad37)") (class "Default")
      (node (ref "PCIE") (pin "37") (pinfunction "PER_P1_37") (pintype "bidirectional"))
    )
    (net (code "268") (name "unconnected-(PCIE-PER_P2-Pad25)") (class "Default")
      (node (ref "PCIE") (pin "25") (pinfunction "PER_P2_25") (pintype "bidirectional"))
    )
    (net (code "269") (name "unconnected-(PCIE-PER_P3-Pad13)") (class "Default")
      (node (ref "PCIE") (pin "13") (pinfunction "PER_P3_13") (pintype "bidirectional"))
    )
    (net (code "270") (name "unconnected-(PCIE-PET_N1-Pad29)") (class "Default")
      (node (ref "PCIE") (pin "29") (pinfunction "PET_N1_29") (pintype "bidirectional"))
    )
    (net (code "271") (name "unconnected-(PCIE-PET_N2-Pad17)") (class "Default")
      (node (ref "PCIE") (pin "17") (pinfunction "PET_N2_17") (pintype "bidirectional"))
    )
    (net (code "272") (name "unconnected-(PCIE-PET_N3-Pad5)") (class "Default")
      (node (ref "PCIE") (pin "5") (pinfunction "PET_N3_5") (pintype "bidirectional"))
    )
    (net (code "273") (name "unconnected-(PCIE-PET_P1-Pad31)") (class "Default")
      (node (ref "PCIE") (pin "31") (pinfunction "PET_P1_31") (pintype "bidirectional"))
    )
    (net (code "274") (name "unconnected-(PCIE-PET_P2-Pad19)") (class "Default")
      (node (ref "PCIE") (pin "19") (pinfunction "PET_P2_19") (pintype "bidirectional"))
    )
    (net (code "275") (name "unconnected-(PCIE-PET_P3-Pad7)") (class "Default")
      (node (ref "PCIE") (pin "7") (pinfunction "PET_P3_7") (pintype "bidirectional"))
    )
    (net (code "276") (name "unconnected-(PI1-Pad63)") (class "Default")
      (node (ref "PI1") (pin "63") (pinfunction "63_63") (pintype "passive"))
    )
    (net (code "277") (name "unconnected-(PI1-Pad67)") (class "Default")
      (node (ref "PI1") (pin "67") (pinfunction "67_67") (pintype "passive"))
    )
    (net (code "278") (name "unconnected-(PI1-Pad69)") (class "Default")
      (node (ref "PI1") (pin "69") (pinfunction "69_69") (pintype "passive"))
    )
    (net (code "279") (name "unconnected-(PI1-Pad71)") (class "Default")
      (node (ref "PI1") (pin "71") (pinfunction "71_71") (pintype "passive"))
    )
    (net (code "280") (name "unconnected-(PI1-Pad74)") (class "Default")
      (node (ref "PI1") (pin "74") (pinfunction "74_74") (pintype "passive"))
    )
    (net (code "281") (name "unconnected-(SD1-DET_A-PadDET1)") (class "Default")
      (node (ref "SD1") (pin "DET1") (pinfunction "DET_A_DET1") (pintype "bidirectional"))
    )
    (net (code "282") (name "unconnected-(SD1-DET_B-PadDET2)") (class "Default")
      (node (ref "SD1") (pin "DET2") (pinfunction "DET_B_DET2") (pintype "bidirectional"))
    )
    (net (code "283") (name "unconnected-(USBC-SBU1-PadA8)") (class "Default")
      (node (ref "USBC") (pin "A8") (pinfunction "SBU1_A8") (pintype "passive"))
    )
    (net (code "284") (name "unconnected-(USBC-SBU2-PadB8)") (class "Default")
      (node (ref "USBC") (pin "B8") (pinfunction "SBU2_B8") (pintype "passive"))
    )
    (net (code "285") (name "~{ADC_RST}") (class "Default")
      (node (ref "CON2") (pin "25") (pinfunction "25_25") (pintype "bidirectional"))
      (node (ref "MODULE_AIO") (pin "A12") (pinfunction "12_A12") (pintype "passive"))
    )
  )
)
